# matrix.net
KiCad netlist of a schematic drawn in Altium Designer
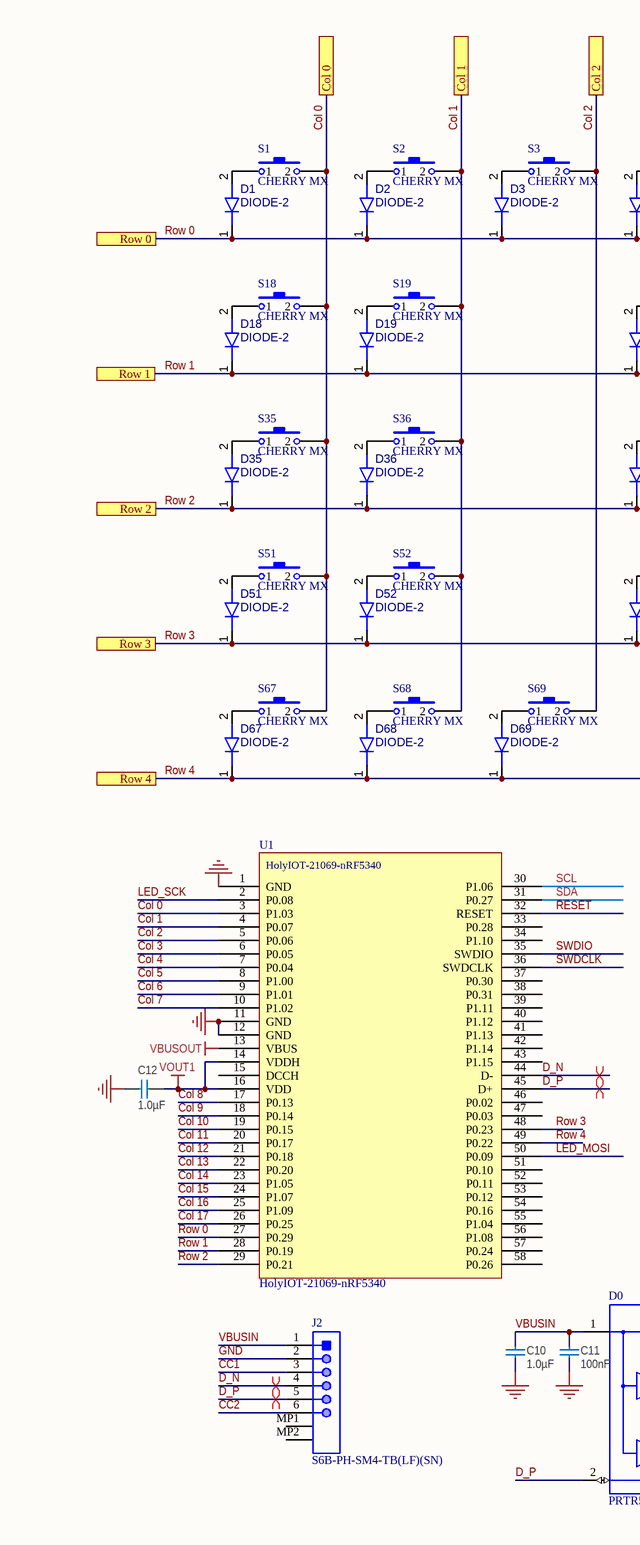
[diagram p0: matrix.SchDoc, left]
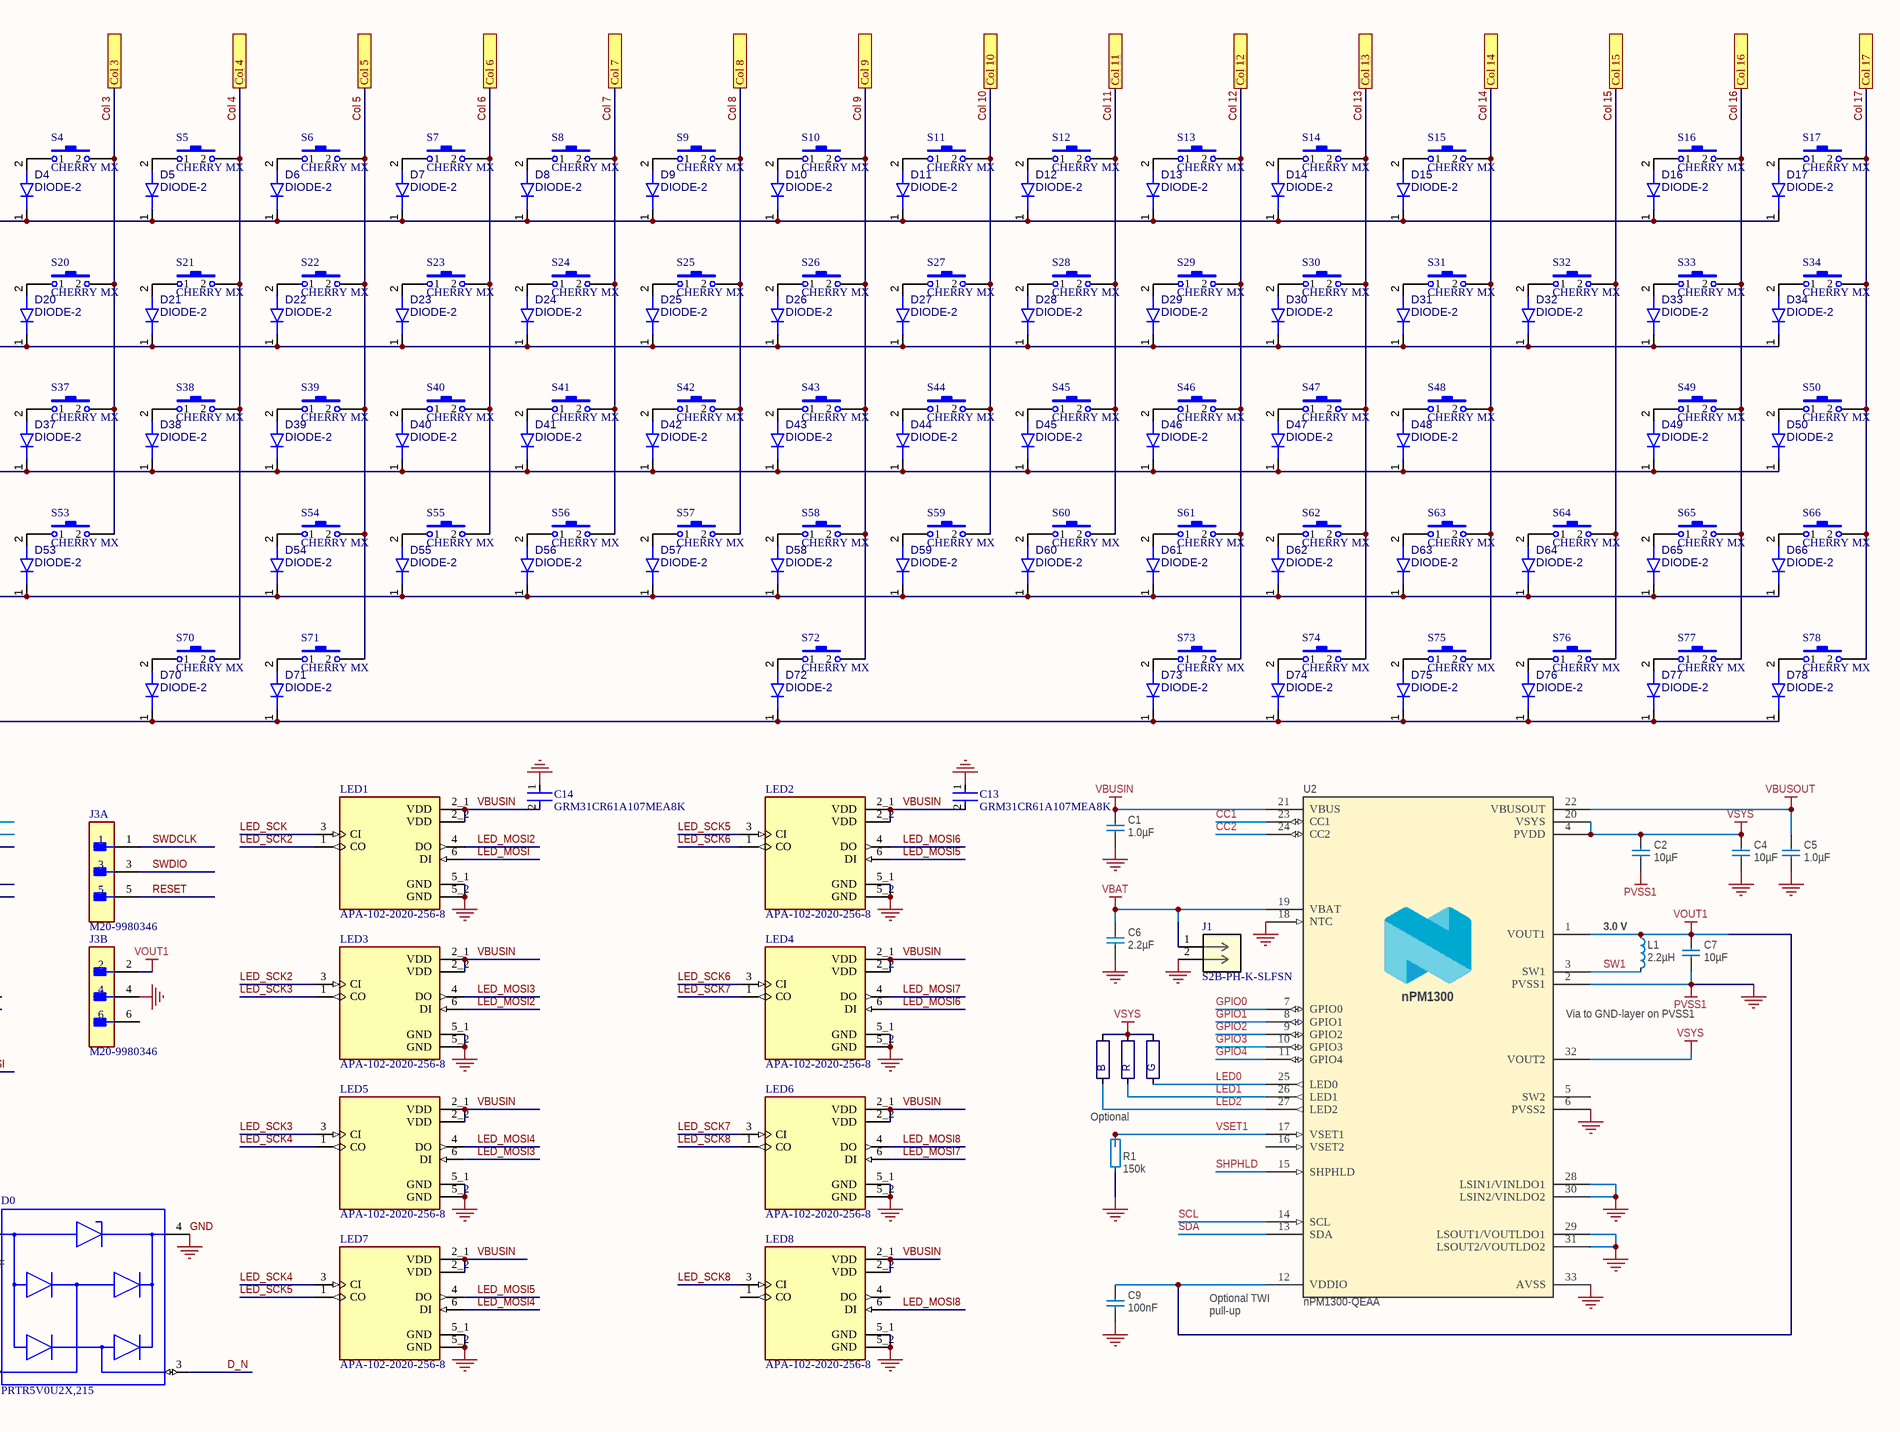
[diagram p1: matrix.SchDoc, right]

(export (version "E")
  (design (tool "Eeschema 10.0.6"))
  (components
    (comp (ref "B") (value "0603") (footprint "CAPC1608X06L") (libsource (lib "mitosis") (part "0603")))
    (comp (ref "C1")
      (value "1.0µF")
      (footprint "CAPC1608X06L")
      (description "Capacitor, Ceramic, 1.0µF 10V X5R 0603,±10%")
      (fields
        (field (name "PART NUMBER") "C0603-1µ0-10V-X5R")
        (field (name "MANUFACTURER") "N.A.")
        (field (name "AUTHOR") "getr")
      )
      (libsource (lib "npm1300_qeaa_config1") (part "C0603-1µ0-10V-X5R"))
    )
    (comp (ref "C2")
      (value "10µF")
      (footprint "CAPC1608X06L")
      (description "Capacitor, X5R, ±20%")
      (fields
        (field (name "PART NUMBER") "C0603-10µ")
        (field (name "MANUFACTURER") "N.A.")
        (field (name "AUTHOR") "rsk")
      )
      (libsource (lib "npm1300_qeaa_config1") (part "CAP"))
    )
    (comp (ref "C4")
      (value "10µF")
      (footprint "CAPC1608X06L")
      (description "Capacitor, X5R, ±20%")
      (fields
        (field (name "PART NUMBER") "C0603-10µ")
        (field (name "MANUFACTURER") "N.A.")
        (field (name "AUTHOR") "rsk")
      )
      (libsource (lib "npm1300_qeaa_config1") (part "CAP"))
    )
    (comp (ref "C5")
      (value "1.0µF")
      (footprint "CAPC1608X06L")
      (description "Capacitor, Ceramic, 1.0µF 10V X5R 0603,±10%")
      (fields
        (field (name "PART NUMBER") "C0603-1µ0-10V-X5R")
        (field (name "MANUFACTURER") "N.A.")
        (field (name "AUTHOR") "getr")
      )
      (libsource (lib "npm1300_qeaa_config1") (part "CAP"))
    )
    (comp (ref "C6")
      (value "2.2µF")
      (footprint "CAPC1608X06L")
      (description "Capacitor, Ceramic, X7R, ±10%, 16V")
      (fields
        (field (name "PART NUMBER") "C0603-2.2µ-16V-X7R")
        (field (name "MANUFACTURER") "Taiyo Yuden")
        (field (name "AUTHOR") "rsk")
      )
      (libsource (lib "npm1300_qeaa_config1") (part "CAP"))
    )
    (comp (ref "C7")
      (value "10µF")
      (footprint "CAPC1608X06L")
      (description "Capacitor, X5R, ±20%")
      (fields
        (field (name "PART NUMBER") "C0603-10µ")
        (field (name "MANUFACTURER") "N.A.")
        (field (name "AUTHOR") "rsk")
      )
      (libsource (lib "npm1300_qeaa_config1") (part "CAP"))
    )
    (comp (ref "C9")
      (value "100nF")
      (footprint "CAPC0603X03L_C")
      (description "Capacitor, X5R, ±10%")
      (fields
        (field (name "PART NUMBER") "C0201-100n")
        (field (name "MANUFACTURER") "N.A.")
        (field (name "AUTHOR") "rsk")
      )
      (libsource (lib "npm1300_qeaa_config1") (part "CAP"))
    )
    (comp (ref "C10")
      (value "1.0µF")
      (footprint "CAPC1608X06L")
      (description "Capacitor, Ceramic, 1.0µF 10V X5R 0603,±10%")
      (fields
        (field (name "PART NUMBER") "C0603-1µ0-10V-X5R")
        (field (name "MANUFACTURER") "N.A.")
        (field (name "AUTHOR") "getr")
      )
      (libsource (lib "npm1300_qeaa_config1") (part "C0603-1µ0-10V-X5R"))
    )
    (comp (ref "C11")
      (value "100nF")
      (footprint "CAPC0603X03L_C")
      (description "Capacitor, X5R, ±10%")
      (fields
        (field (name "PART NUMBER") "C0201-100n")
        (field (name "MANUFACTURER") "N.A.")
        (field (name "AUTHOR") "rsk")
      )
      (libsource (lib "npm1300_qeaa_config1") (part "C0201-100n"))
    )
    (comp (ref "C12")
      (value "1.0µF")
      (footprint "CAPC1608X06L")
      (description "Capacitor, Ceramic, 1.0µF 10V X5R 0603,±10%")
      (fields
        (field (name "PART NUMBER") "C0603-1µ0-10V-X5R")
        (field (name "MANUFACTURER") "N.A.")
        (field (name "AUTHOR") "getr")
      )
      (libsource (lib "npm1300_qeaa_config1") (part "C0603-1µ0-10V-X5R"))
    )
    (comp (ref "C13")
      (value "GRM31CR61A107MEA8K")
      (footprint "FP-GRM31C-0_3-e0_3_0_8-MFG")
      (description "Chip Multilayer Ceramic Capacitors for General Purpose, 1206, 100uF, X5R, 15%, 20%, 10V")
      (libsource (lib "Altium Content Vault") (part "f23184f103b6ebe33a8c269c53dcba6"))
    )
    (comp (ref "C14")
      (value "GRM31CR61A107MEA8K")
      (footprint "FP-GRM31C-0_3-e0_3_0_8-MFG")
      (description "Chip Multilayer Ceramic Capacitors for General Purpose, 1206, 100uF, X5R, 15%, 20%, 10V")
      (libsource (lib "Altium Content Vault") (part "f23184f103b6ebe33a8c269c53dcba6"))
    )
    (comp (ref "D0")
      (value "PRTR5V0U2X,215")
      (footprint "FP-SOT143B-MFG")
      (description "Trans Voltage Suppressor Diode, 5.5V V(RWM), Unidirectional, 1 Element, Silicon")
      (libsource (lib "NUSolar") (part "31e4fa1655694efd507c8a671e666ef"))
    )
    (comp (ref "D1")
      (value "DIODE-2")
      (footprint "1N4148")
      (description "Diode")
      (libsource (lib "mitosis") (part "1N4148"))
    )
    (comp (ref "D2")
      (value "DIODE-2")
      (footprint "1N4148")
      (description "Diode")
      (libsource (lib "mitosis") (part "1N4148"))
    )
    (comp (ref "D3")
      (value "DIODE-2")
      (footprint "1N4148")
      (description "Diode")
      (libsource (lib "mitosis") (part "1N4148"))
    )
    (comp (ref "D4")
      (value "DIODE-2")
      (footprint "1N4148")
      (description "Diode")
      (libsource (lib "mitosis") (part "1N4148"))
    )
    (comp (ref "D5")
      (value "DIODE-2")
      (footprint "1N4148")
      (description "Diode")
      (libsource (lib "mitosis") (part "1N4148"))
    )
    (comp (ref "D6")
      (value "DIODE-2")
      (footprint "1N4148")
      (description "Diode")
      (libsource (lib "mitosis") (part "1N4148"))
    )
    (comp (ref "D7")
      (value "DIODE-2")
      (footprint "1N4148")
      (description "Diode")
      (libsource (lib "mitosis") (part "1N4148"))
    )
    (comp (ref "D8")
      (value "DIODE-2")
      (footprint "1N4148")
      (description "Diode")
      (libsource (lib "mitosis") (part "1N4148"))
    )
    (comp (ref "D9")
      (value "DIODE-2")
      (footprint "1N4148")
      (description "Diode")
      (libsource (lib "mitosis") (part "1N4148"))
    )
    (comp (ref "D10")
      (value "DIODE-2")
      (footprint "1N4148")
      (description "Diode")
      (libsource (lib "mitosis") (part "1N4148"))
    )
    (comp (ref "D11")
      (value "DIODE-2")
      (footprint "1N4148")
      (description "Diode")
      (libsource (lib "mitosis") (part "1N4148"))
    )
    (comp (ref "D12")
      (value "DIODE-2")
      (footprint "1N4148")
      (description "Diode")
      (libsource (lib "mitosis") (part "1N4148"))
    )
    (comp (ref "D13")
      (value "DIODE-2")
      (footprint "1N4148")
      (description "Diode")
      (libsource (lib "mitosis") (part "1N4148"))
    )
    (comp (ref "D14")
      (value "DIODE-2")
      (footprint "1N4148")
      (description "Diode")
      (libsource (lib "mitosis") (part "1N4148"))
    )
    (comp (ref "D15")
      (value "DIODE-2")
      (footprint "1N4148")
      (description "Diode")
      (libsource (lib "mitosis") (part "1N4148"))
    )
    (comp (ref "D16")
      (value "DIODE-2")
      (footprint "1N4148")
      (description "Diode")
      (libsource (lib "mitosis") (part "1N4148"))
    )
    (comp (ref "D17")
      (value "DIODE-2")
      (footprint "1N4148")
      (description "Diode")
      (libsource (lib "mitosis") (part "1N4148"))
    )
    (comp (ref "D18")
      (value "DIODE-2")
      (footprint "1N4148")
      (description "Diode")
      (libsource (lib "mitosis") (part "1N4148"))
    )
    (comp (ref "D19")
      (value "DIODE-2")
      (footprint "1N4148")
      (description "Diode")
      (libsource (lib "mitosis") (part "1N4148"))
    )
    (comp (ref "D20")
      (value "DIODE-2")
      (footprint "1N4148")
      (description "Diode")
      (libsource (lib "mitosis") (part "1N4148"))
    )
    (comp (ref "D21")
      (value "DIODE-2")
      (footprint "1N4148")
      (description "Diode")
      (libsource (lib "mitosis") (part "1N4148"))
    )
    (comp (ref "D22")
      (value "DIODE-2")
      (footprint "1N4148")
      (description "Diode")
      (libsource (lib "mitosis") (part "1N4148"))
    )
    (comp (ref "D23")
      (value "DIODE-2")
      (footprint "1N4148")
      (description "Diode")
      (libsource (lib "mitosis") (part "1N4148"))
    )
    (comp (ref "D24")
      (value "DIODE-2")
      (footprint "1N4148")
      (description "Diode")
      (libsource (lib "mitosis") (part "1N4148"))
    )
    (comp (ref "D25")
      (value "DIODE-2")
      (footprint "1N4148")
      (description "Diode")
      (libsource (lib "mitosis") (part "1N4148"))
    )
    (comp (ref "D26")
      (value "DIODE-2")
      (footprint "1N4148")
      (description "Diode")
      (libsource (lib "mitosis") (part "1N4148"))
    )
    (comp (ref "D27")
      (value "DIODE-2")
      (footprint "1N4148")
      (description "Diode")
      (libsource (lib "mitosis") (part "1N4148"))
    )
    (comp (ref "D28")
      (value "DIODE-2")
      (footprint "1N4148")
      (description "Diode")
      (libsource (lib "mitosis") (part "1N4148"))
    )
    (comp (ref "D29")
      (value "DIODE-2")
      (footprint "1N4148")
      (description "Diode")
      (libsource (lib "mitosis") (part "1N4148"))
    )
    (comp (ref "D30")
      (value "DIODE-2")
      (footprint "1N4148")
      (description "Diode")
      (libsource (lib "mitosis") (part "1N4148"))
    )
    (comp (ref "D31")
      (value "DIODE-2")
      (footprint "1N4148")
      (description "Diode")
      (libsource (lib "mitosis") (part "1N4148"))
    )
    (comp (ref "D32")
      (value "DIODE-2")
      (footprint "1N4148")
      (description "Diode")
      (libsource (lib "mitosis") (part "1N4148"))
    )
    (comp (ref "D33")
      (value "DIODE-2")
      (footprint "1N4148")
      (description "Diode")
      (libsource (lib "mitosis") (part "1N4148"))
    )
    (comp (ref "D34")
      (value "DIODE-2")
      (footprint "1N4148")
      (description "Diode")
      (libsource (lib "mitosis") (part "1N4148"))
    )
    (comp (ref "D35")
      (value "DIODE-2")
      (footprint "1N4148")
      (description "Diode")
      (libsource (lib "mitosis") (part "1N4148"))
    )
    (comp (ref "D36")
      (value "DIODE-2")
      (footprint "1N4148")
      (description "Diode")
      (libsource (lib "mitosis") (part "1N4148"))
    )
    (comp (ref "D37")
      (value "DIODE-2")
      (footprint "1N4148")
      (description "Diode")
      (libsource (lib "mitosis") (part "1N4148"))
    )
    (comp (ref "D38")
      (value "DIODE-2")
      (footprint "1N4148")
      (description "Diode")
      (libsource (lib "mitosis") (part "1N4148"))
    )
    (comp (ref "D39")
      (value "DIODE-2")
      (footprint "1N4148")
      (description "Diode")
      (libsource (lib "mitosis") (part "1N4148"))
    )
    (comp (ref "D40")
      (value "DIODE-2")
      (footprint "1N4148")
      (description "Diode")
      (libsource (lib "mitosis") (part "1N4148"))
    )
    (comp (ref "D41")
      (value "DIODE-2")
      (footprint "1N4148")
      (description "Diode")
      (libsource (lib "mitosis") (part "1N4148"))
    )
    (comp (ref "D42")
      (value "DIODE-2")
      (footprint "1N4148")
      (description "Diode")
      (libsource (lib "mitosis") (part "1N4148"))
    )
    (comp (ref "D43")
      (value "DIODE-2")
      (footprint "1N4148")
      (description "Diode")
      (libsource (lib "mitosis") (part "1N4148"))
    )
    (comp (ref "D44")
      (value "DIODE-2")
      (footprint "1N4148")
      (description "Diode")
      (libsource (lib "mitosis") (part "1N4148"))
    )
    (comp (ref "D45")
      (value "DIODE-2")
      (footprint "1N4148")
      (description "Diode")
      (libsource (lib "mitosis") (part "1N4148"))
    )
    (comp (ref "D46")
      (value "DIODE-2")
      (footprint "1N4148")
      (description "Diode")
      (libsource (lib "mitosis") (part "1N4148"))
    )
    (comp (ref "D47")
      (value "DIODE-2")
      (footprint "1N4148")
      (description "Diode")
      (libsource (lib "mitosis") (part "1N4148"))
    )
    (comp (ref "D48")
      (value "DIODE-2")
      (footprint "1N4148")
      (description "Diode")
      (libsource (lib "mitosis") (part "1N4148"))
    )
    (comp (ref "D49")
      (value "DIODE-2")
      (footprint "1N4148")
      (description "Diode")
      (libsource (lib "mitosis") (part "1N4148"))
    )
    (comp (ref "D50")
      (value "DIODE-2")
      (footprint "1N4148")
      (description "Diode")
      (libsource (lib "mitosis") (part "1N4148"))
    )
    (comp (ref "D51")
      (value "DIODE-2")
      (footprint "1N4148")
      (description "Diode")
      (libsource (lib "mitosis") (part "1N4148"))
    )
    (comp (ref "D52")
      (value "DIODE-2")
      (footprint "1N4148")
      (description "Diode")
      (libsource (lib "mitosis") (part "1N4148"))
    )
    (comp (ref "D53")
      (value "DIODE-2")
      (footprint "1N4148")
      (description "Diode")
      (libsource (lib "mitosis") (part "1N4148"))
    )
    (comp (ref "D54")
      (value "DIODE-2")
      (footprint "1N4148")
      (description "Diode")
      (libsource (lib "mitosis") (part "1N4148"))
    )
    (comp (ref "D55")
      (value "DIODE-2")
      (footprint "1N4148")
      (description "Diode")
      (libsource (lib "mitosis") (part "1N4148"))
    )
    (comp (ref "D56")
      (value "DIODE-2")
      (footprint "1N4148")
      (description "Diode")
      (libsource (lib "mitosis") (part "1N4148"))
    )
    (comp (ref "D57")
      (value "DIODE-2")
      (footprint "1N4148")
      (description "Diode")
      (libsource (lib "mitosis") (part "1N4148"))
    )
    (comp (ref "D58")
      (value "DIODE-2")
      (footprint "1N4148")
      (description "Diode")
      (libsource (lib "mitosis") (part "1N4148"))
    )
    (comp (ref "D59")
      (value "DIODE-2")
      (footprint "1N4148")
      (description "Diode")
      (libsource (lib "mitosis") (part "1N4148"))
    )
    (comp (ref "D60")
      (value "DIODE-2")
      (footprint "1N4148")
      (description "Diode")
      (libsource (lib "mitosis") (part "1N4148"))
    )
    (comp (ref "D61")
      (value "DIODE-2")
      (footprint "1N4148")
      (description "Diode")
      (libsource (lib "mitosis") (part "1N4148"))
    )
    (comp (ref "D62")
      (value "DIODE-2")
      (footprint "1N4148")
      (description "Diode")
      (libsource (lib "mitosis") (part "1N4148"))
    )
    (comp (ref "D63")
      (value "DIODE-2")
      (footprint "1N4148")
      (description "Diode")
      (libsource (lib "mitosis") (part "1N4148"))
    )
    (comp (ref "D64")
      (value "DIODE-2")
      (footprint "1N4148")
      (description "Diode")
      (libsource (lib "mitosis") (part "1N4148"))
    )
    (comp (ref "D65")
      (value "DIODE-2")
      (footprint "1N4148")
      (description "Diode")
      (libsource (lib "mitosis") (part "1N4148"))
    )
    (comp (ref "D66")
      (value "DIODE-2")
      (footprint "1N4148")
      (description "Diode")
      (libsource (lib "mitosis") (part "1N4148"))
    )
    (comp (ref "D67")
      (value "DIODE-2")
      (footprint "1N4148")
      (description "Diode")
      (libsource (lib "mitosis") (part "1N4148"))
    )
    (comp (ref "D68")
      (value "DIODE-2")
      (footprint "1N4148")
      (description "Diode")
      (libsource (lib "mitosis") (part "1N4148"))
    )
    (comp (ref "D69")
      (value "DIODE-2")
      (footprint "1N4148")
      (description "Diode")
      (libsource (lib "mitosis") (part "1N4148"))
    )
    (comp (ref "D70")
      (value "DIODE-2")
      (footprint "1N4148")
      (description "Diode")
      (libsource (lib "mitosis") (part "1N4148"))
    )
    (comp (ref "D71")
      (value "DIODE-2")
      (footprint "1N4148")
      (description "Diode")
      (libsource (lib "mitosis") (part "1N4148"))
    )
    (comp (ref "D72")
      (value "DIODE-2")
      (footprint "1N4148")
      (description "Diode")
      (libsource (lib "mitosis") (part "1N4148"))
    )
    (comp (ref "D73")
      (value "DIODE-2")
      (footprint "1N4148")
      (description "Diode")
      (libsource (lib "mitosis") (part "1N4148"))
    )
    (comp (ref "D74")
      (value "DIODE-2")
      (footprint "1N4148")
      (description "Diode")
      (libsource (lib "mitosis") (part "1N4148"))
    )
    (comp (ref "D75")
      (value "DIODE-2")
      (footprint "1N4148")
      (description "Diode")
      (libsource (lib "mitosis") (part "1N4148"))
    )
    (comp (ref "D76")
      (value "DIODE-2")
      (footprint "1N4148")
      (description "Diode")
      (libsource (lib "mitosis") (part "1N4148"))
    )
    (comp (ref "D77")
      (value "DIODE-2")
      (footprint "1N4148")
      (description "Diode")
      (libsource (lib "mitosis") (part "1N4148"))
    )
    (comp (ref "D78")
      (value "DIODE-2")
      (footprint "1N4148")
      (description "Diode")
      (libsource (lib "mitosis") (part "1N4148"))
    )
    (comp (ref "G") (value "0603") (footprint "CAPC1608X06L") (libsource (lib "mitosis") (part "0603")))
    (comp (ref "J1")
      (value "S2B-PH-K-SLFSN")
      (footprint "CONN_S2B-PH-K-S_JST")
      (description "No Description Available")
      (libsource (lib "mitosis") (part "S2B-PH-K-SLFSN"))
    )
    (comp (ref "J2")
      (value "S6B-PH-SM4-TB(LF)(SN)")
      (footprint "JST-S6B-PH-SM4-TB(LF)(SN)_V")
      (description "Male Header, Pitch 2 mm, 1 x 6 Position, Height 5.5 mm, -25 to 85 degC")
      (fields (field (name "MANUFACTURER") "JST"))
      (libsource (lib "mitosis") (part "S6B-PH-SM4-TB"))
    )
    (comp (ref "J3")
      (value "M20-9980346")
      (footprint "FP-M20-9980346-MFG")
      (description "CONN HEADER VERT 6POS 2.54MM")
      (fields
        (field (name "MANUFACTURER") "Harwin")
        (field (name "OCTOPART") "https://octopart.com/m20-9980346-harwin-5436545")
      )
      (libsource (lib "mitosis") (part "CMP-2000-06636-2"))
    )
    (comp (ref "L1")
      (value "2.2µH")
      (footprint "INDC2016X10N")
      (description "Inductor, Irms=2.5A, Isat=2.9A, ±20%, DCR=73mΩ")
      (fields
        (field (name "PART NUMBER") "L0806-2µ2-2500mA-73mOhm-CIGT201610EH2R2MNE")
        (field (name "MANUFACTURER") "Samsung Electro-Mechanics")
        (field (name "AUTHOR") "rsk")
      )
      (libsource (lib "npm1300_qeaa_config1") (part "IND"))
    )
    (comp (ref "LED1")
      (value "APA-102-2020-256-8")
      (footprint "LED_APA-102-2020-256-8")
      (description "8-pin type LED three-color RGB Dimming control")
      (fields (field (name "MF") "iPixel LED Light Co."))
      (libsource (lib "mitosis") (part "APA-102-2020-256-8"))
    )
    (comp (ref "LED2")
      (value "APA-102-2020-256-8")
      (footprint "LED_APA-102-2020-256-8")
      (description "8-pin type LED three-color RGB Dimming control")
      (fields (field (name "MF") "iPixel LED Light Co."))
      (libsource (lib "mitosis") (part "APA-102-2020-256-8"))
    )
    (comp (ref "LED3")
      (value "APA-102-2020-256-8")
      (footprint "LED_APA-102-2020-256-8")
      (description "8-pin type LED three-color RGB Dimming control")
      (fields (field (name "MF") "iPixel LED Light Co."))
      (libsource (lib "mitosis") (part "APA-102-2020-256-8"))
    )
    (comp (ref "LED4")
      (value "APA-102-2020-256-8")
      (footprint "LED_APA-102-2020-256-8")
      (description "8-pin type LED three-color RGB Dimming control")
      (fields (field (name "MF") "iPixel LED Light Co."))
      (libsource (lib "mitosis") (part "APA-102-2020-256-8"))
    )
    (comp (ref "LED5")
      (value "APA-102-2020-256-8")
      (footprint "LED_APA-102-2020-256-8")
      (description "8-pin type LED three-color RGB Dimming control")
      (fields (field (name "MF") "iPixel LED Light Co."))
      (libsource (lib "mitosis") (part "APA-102-2020-256-8"))
    )
    (comp (ref "LED6")
      (value "APA-102-2020-256-8")
      (footprint "LED_APA-102-2020-256-8")
      (description "8-pin type LED three-color RGB Dimming control")
      (fields (field (name "MF") "iPixel LED Light Co."))
      (libsource (lib "mitosis") (part "APA-102-2020-256-8"))
    )
    (comp (ref "LED7")
      (value "APA-102-2020-256-8")
      (footprint "LED_APA-102-2020-256-8")
      (description "8-pin type LED three-color RGB Dimming control")
      (fields (field (name "MF") "iPixel LED Light Co."))
      (libsource (lib "mitosis") (part "APA-102-2020-256-8"))
    )
    (comp (ref "LED8")
      (value "APA-102-2020-256-8")
      (footprint "LED_APA-102-2020-256-8")
      (description "8-pin type LED three-color RGB Dimming control")
      (fields (field (name "MF") "iPixel LED Light Co."))
      (libsource (lib "mitosis") (part "APA-102-2020-256-8"))
    )
    (comp (ref "R") (value "0603") (footprint "CAPC1608X06L") (libsource (lib "mitosis") (part "0603")))
    (comp (ref "R1")
      (value "150k")
      (footprint "RESC0603X03L_C")
      (description "Resistor, ±1%, 0.05W")
      (fields
        (field (name "PART NUMBER") "R0201-150k")
        (field (name "MANUFACTURER") "N.A.")
        (field (name "AUTHOR") "rsk")
      )
      (libsource (lib "npm1300_qeaa_config1") (part "R0201-150k"))
    )
    (comp (ref "S1")
      (value "CHERRY MX")
      (footprint "1u-CHERRY-SMK-CUTOUT")
      (description "Switch")
      (fields (field (name "PUBLISHER") "Altium Limited"))
      (libsource (lib "mitosis") (part "CHERRY MX"))
    )
    (comp (ref "S2")
      (value "CHERRY MX")
      (footprint "1u-CHERRY-SMK-CUTOUT")
      (description "Switch")
      (fields (field (name "PUBLISHER") "Altium Limited"))
      (libsource (lib "mitosis") (part "CHERRY MX"))
    )
    (comp (ref "S3")
      (value "CHERRY MX")
      (footprint "1u-CHERRY-SMK-CUTOUT")
      (description "Switch")
      (fields (field (name "PUBLISHER") "Altium Limited"))
      (libsource (lib "mitosis") (part "CHERRY MX"))
    )
    (comp (ref "S4")
      (value "CHERRY MX")
      (footprint "1u-CHERRY-SMK-CUTOUT")
      (description "Switch")
      (fields (field (name "PUBLISHER") "Altium Limited"))
      (libsource (lib "mitosis") (part "CHERRY MX"))
    )
    (comp (ref "S5")
      (value "CHERRY MX")
      (footprint "1u-CHERRY-SMK-CUTOUT")
      (description "Switch")
      (fields (field (name "PUBLISHER") "Altium Limited"))
      (libsource (lib "mitosis") (part "CHERRY MX"))
    )
    (comp (ref "S6")
      (value "CHERRY MX")
      (footprint "1u-CHERRY-SMK-CUTOUT")
      (description "Switch")
      (fields (field (name "PUBLISHER") "Altium Limited"))
      (libsource (lib "mitosis") (part "CHERRY MX"))
    )
    (comp (ref "S7")
      (value "CHERRY MX")
      (footprint "1u-CHERRY-SMK-CUTOUT")
      (description "Switch")
      (fields (field (name "PUBLISHER") "Altium Limited"))
      (libsource (lib "mitosis") (part "CHERRY MX"))
    )
    (comp (ref "S8")
      (value "CHERRY MX")
      (footprint "1u-CHERRY-SMK-CUTOUT")
      (description "Switch")
      (fields (field (name "PUBLISHER") "Altium Limited"))
      (libsource (lib "mitosis") (part "CHERRY MX"))
    )
    (comp (ref "S9")
      (value "CHERRY MX")
      (footprint "1u-CHERRY-SMK-CUTOUT")
      (description "Switch")
      (fields (field (name "PUBLISHER") "Altium Limited"))
      (libsource (lib "mitosis") (part "CHERRY MX"))
    )
    (comp (ref "S10")
      (value "CHERRY MX")
      (footprint "1u-CHERRY-SMK-CUTOUT")
      (description "Switch")
      (fields (field (name "PUBLISHER") "Altium Limited"))
      (libsource (lib "mitosis") (part "CHERRY MX"))
    )
    (comp (ref "S11")
      (value "CHERRY MX")
      (footprint "1u-CHERRY-SMK-CUTOUT")
      (description "Switch")
      (fields (field (name "PUBLISHER") "Altium Limited"))
      (libsource (lib "mitosis") (part "CHERRY MX"))
    )
    (comp (ref "S12")
      (value "CHERRY MX")
      (footprint "1u-CHERRY-SMK-CUTOUT")
      (description "Switch")
      (fields (field (name "PUBLISHER") "Altium Limited"))
      (libsource (lib "mitosis") (part "CHERRY MX"))
    )
    (comp (ref "S13")
      (value "CHERRY MX")
      (footprint "1u-CHERRY-SMK-CUTOUT")
      (description "Switch")
      (fields (field (name "PUBLISHER") "Altium Limited"))
      (libsource (lib "mitosis") (part "CHERRY MX"))
    )
    (comp (ref "S14")
      (value "CHERRY MX")
      (footprint "1u-CHERRY-SMK-CUTOUT")
      (description "Switch")
      (fields (field (name "PUBLISHER") "Altium Limited"))
      (libsource (lib "mitosis") (part "CHERRY MX"))
    )
    (comp (ref "S15")
      (value "CHERRY MX")
      (footprint "1u-CHERRY-SMK-CUTOUT")
      (description "Switch")
      (fields (field (name "PUBLISHER") "Altium Limited"))
      (libsource (lib "mitosis") (part "CHERRY MX"))
    )
    (comp (ref "S16")
      (value "CHERRY MX")
      (footprint "2u-STAB-CHERRY-SMK-CUTOUT")
      (description "Switch")
      (fields (field (name "PUBLISHER") "Altium Limited"))
      (libsource (lib "mitosis") (part "CHERRY MX"))
    )
    (comp (ref "S17")
      (value "CHERRY MX")
      (footprint "1u-CHERRY-SMK-CUTOUT")
      (description "Switch")
      (fields (field (name "PUBLISHER") "Altium Limited"))
      (libsource (lib "mitosis") (part "CHERRY MX"))
    )
    (comp (ref "S18")
      (value "CHERRY MX")
      (footprint "1u-CHERRY-SMK-CUTOUT")
      (description "Switch")
      (fields (field (name "PUBLISHER") "Altium Limited"))
      (libsource (lib "mitosis") (part "CHERRY MX"))
    )
    (comp (ref "S19")
      (value "CHERRY MX")
      (footprint "1u-CHERRY-SMK-CUTOUT")
      (description "Switch")
      (fields (field (name "PUBLISHER") "Altium Limited"))
      (libsource (lib "mitosis") (part "CHERRY MX"))
    )
    (comp (ref "S20")
      (value "CHERRY MX")
      (footprint "1.5u-CHERRY-SMK-CUTOUT")
      (description "Switch")
      (fields (field (name "PUBLISHER") "Altium Limited"))
      (libsource (lib "mitosis") (part "CHERRY MX"))
    )
    (comp (ref "S21")
      (value "CHERRY MX")
      (footprint "1u-CHERRY-SMK-CUTOUT")
      (description "Switch")
      (fields (field (name "PUBLISHER") "Altium Limited"))
      (libsource (lib "mitosis") (part "CHERRY MX"))
    )
    (comp (ref "S22")
      (value "CHERRY MX")
      (footprint "1u-CHERRY-SMK-CUTOUT")
      (description "Switch")
      (fields (field (name "PUBLISHER") "Altium Limited"))
      (libsource (lib "mitosis") (part "CHERRY MX"))
    )
    (comp (ref "S23")
      (value "CHERRY MX")
      (footprint "1u-CHERRY-SMK-CUTOUT")
      (description "Switch")
      (fields (field (name "PUBLISHER") "Altium Limited"))
      (libsource (lib "mitosis") (part "CHERRY MX"))
    )
    (comp (ref "S24")
      (value "CHERRY MX")
      (footprint "1u-CHERRY-SMK-CUTOUT")
      (description "Switch")
      (fields (field (name "PUBLISHER") "Altium Limited"))
      (libsource (lib "mitosis") (part "CHERRY MX"))
    )
    (comp (ref "S25")
      (value "CHERRY MX")
      (footprint "1u-CHERRY-SMK-CUTOUT")
      (description "Switch")
      (fields (field (name "PUBLISHER") "Altium Limited"))
      (libsource (lib "mitosis") (part "CHERRY MX"))
    )
    (comp (ref "S26")
      (value "CHERRY MX")
      (footprint "1u-CHERRY-SMK-CUTOUT")
      (description "Switch")
      (fields (field (name "PUBLISHER") "Altium Limited"))
      (libsource (lib "mitosis") (part "CHERRY MX"))
    )
    (comp (ref "S27")
      (value "CHERRY MX")
      (footprint "1u-CHERRY-SMK-CUTOUT")
      (description "Switch")
      (fields (field (name "PUBLISHER") "Altium Limited"))
      (libsource (lib "mitosis") (part "CHERRY MX"))
    )
    (comp (ref "S28")
      (value "CHERRY MX")
      (footprint "1u-CHERRY-SMK-CUTOUT")
      (description "Switch")
      (fields (field (name "PUBLISHER") "Altium Limited"))
      (libsource (lib "mitosis") (part "CHERRY MX"))
    )
    (comp (ref "S29")
      (value "CHERRY MX")
      (footprint "1u-CHERRY-SMK-CUTOUT")
      (description "Switch")
      (fields (field (name "PUBLISHER") "Altium Limited"))
      (libsource (lib "mitosis") (part "CHERRY MX"))
    )
    (comp (ref "S30")
      (value "CHERRY MX")
      (footprint "1u-CHERRY-SMK-CUTOUT")
      (description "Switch")
      (fields (field (name "PUBLISHER") "Altium Limited"))
      (libsource (lib "mitosis") (part "CHERRY MX"))
    )
    (comp (ref "S31")
      (value "CHERRY MX")
      (footprint "1u-CHERRY-SMK-CUTOUT")
      (description "Switch")
      (fields (field (name "PUBLISHER") "Altium Limited"))
      (libsource (lib "mitosis") (part "CHERRY MX"))
    )
    (comp (ref "S32")
      (value "CHERRY MX")
      (footprint "1u-CHERRY-SMK-CUTOUT")
      (description "Switch")
      (fields (field (name "PUBLISHER") "Altium Limited"))
      (libsource (lib "mitosis") (part "CHERRY MX"))
    )
    (comp (ref "S33")
      (value "CHERRY MX")
      (footprint "1.5u-CHERRY-SMK-CUTOUT")
      (description "Switch")
      (fields (field (name "PUBLISHER") "Altium Limited"))
      (libsource (lib "mitosis") (part "CHERRY MX"))
    )
    (comp (ref "S34")
      (value "CHERRY MX")
      (footprint "1u-CHERRY-SMK-CUTOUT")
      (description "Switch")
      (fields (field (name "PUBLISHER") "Altium Limited"))
      (libsource (lib "mitosis") (part "CHERRY MX"))
    )
    (comp (ref "S35")
      (value "CHERRY MX")
      (footprint "1u-CHERRY-SMK-CUTOUT")
      (description "Switch")
      (fields (field (name "PUBLISHER") "Altium Limited"))
      (libsource (lib "mitosis") (part "CHERRY MX"))
    )
    (comp (ref "S36")
      (value "CHERRY MX")
      (footprint "1u-CHERRY-SMK-CUTOUT")
      (description "Switch")
      (fields (field (name "PUBLISHER") "Altium Limited"))
      (libsource (lib "mitosis") (part "CHERRY MX"))
    )
    (comp (ref "S37")
      (value "CHERRY MX")
      (footprint "1.75u-CHERRY-SMK-CUTOUT")
      (description "Switch")
      (fields (field (name "PUBLISHER") "Altium Limited"))
      (libsource (lib "mitosis") (part "CHERRY MX"))
    )
    (comp (ref "S38")
      (value "CHERRY MX")
      (footprint "1u-CHERRY-SMK-CUTOUT")
      (description "Switch")
      (fields (field (name "PUBLISHER") "Altium Limited"))
      (libsource (lib "mitosis") (part "CHERRY MX"))
    )
    (comp (ref "S39")
      (value "CHERRY MX")
      (footprint "1u-CHERRY-SMK-CUTOUT")
      (description "Switch")
      (fields (field (name "PUBLISHER") "Altium Limited"))
      (libsource (lib "mitosis") (part "CHERRY MX"))
    )
    (comp (ref "S40")
      (value "CHERRY MX")
      (footprint "1u-CHERRY-SMK-CUTOUT")
      (description "Switch")
      (fields (field (name "PUBLISHER") "Altium Limited"))
      (libsource (lib "mitosis") (part "CHERRY MX"))
    )
    (comp (ref "S41")
      (value "CHERRY MX")
      (footprint "1u-CHERRY-SMK-CUTOUT")
      (description "Switch")
      (fields (field (name "PUBLISHER") "Altium Limited"))
      (libsource (lib "mitosis") (part "CHERRY MX"))
    )
    (comp (ref "S42")
      (value "CHERRY MX")
      (footprint "1u-CHERRY-SMK-CUTOUT")
      (description "Switch")
      (fields (field (name "PUBLISHER") "Altium Limited"))
      (libsource (lib "mitosis") (part "CHERRY MX"))
    )
    (comp (ref "S43")
      (value "CHERRY MX")
      (footprint "1u-CHERRY-SMK-CUTOUT")
      (description "Switch")
      (fields (field (name "PUBLISHER") "Altium Limited"))
      (libsource (lib "mitosis") (part "CHERRY MX"))
    )
    (comp (ref "S44")
      (value "CHERRY MX")
      (footprint "1u-CHERRY-SMK-CUTOUT")
      (description "Switch")
      (fields (field (name "PUBLISHER") "Altium Limited"))
      (libsource (lib "mitosis") (part "CHERRY MX"))
    )
    (comp (ref "S45")
      (value "CHERRY MX")
      (footprint "1u-CHERRY-SMK-CUTOUT")
      (description "Switch")
      (fields (field (name "PUBLISHER") "Altium Limited"))
      (libsource (lib "mitosis") (part "CHERRY MX"))
    )
    (comp (ref "S46")
      (value "CHERRY MX")
      (footprint "1u-CHERRY-SMK-CUTOUT")
      (description "Switch")
      (fields (field (name "PUBLISHER") "Altium Limited"))
      (libsource (lib "mitosis") (part "CHERRY MX"))
    )
    (comp (ref "S47")
      (value "CHERRY MX")
      (footprint "1u-CHERRY-SMK-CUTOUT")
      (description "Switch")
      (fields (field (name "PUBLISHER") "Altium Limited"))
      (libsource (lib "mitosis") (part "CHERRY MX"))
    )
    (comp (ref "S48")
      (value "CHERRY MX")
      (footprint "1u-CHERRY-SMK-CUTOUT")
      (description "Switch")
      (fields (field (name "PUBLISHER") "Altium Limited"))
      (libsource (lib "mitosis") (part "CHERRY MX"))
    )
    (comp (ref "S49")
      (value "CHERRY MX")
      (footprint "2.25u-STAB-CHERRY-SMK-CUTOUT")
      (description "Switch")
      (fields (field (name "PUBLISHER") "Altium Limited"))
      (libsource (lib "mitosis") (part "CHERRY MX"))
    )
    (comp (ref "S50")
      (value "CHERRY MX")
      (footprint "1u-CHERRY-SMK-CUTOUT")
      (description "Switch")
      (fields (field (name "PUBLISHER") "Altium Limited"))
      (libsource (lib "mitosis") (part "CHERRY MX"))
    )
    (comp (ref "S51")
      (value "CHERRY MX")
      (footprint "1u-CHERRY-SMK-CUTOUT")
      (description "Switch")
      (fields (field (name "PUBLISHER") "Altium Limited"))
      (libsource (lib "mitosis") (part "CHERRY MX"))
    )
    (comp (ref "S52")
      (value "CHERRY MX")
      (footprint "1u-CHERRY-SMK-CUTOUT")
      (description "Switch")
      (fields (field (name "PUBLISHER") "Altium Limited"))
      (libsource (lib "mitosis") (part "CHERRY MX"))
    )
    (comp (ref "S53")
      (value "CHERRY MX")
      (footprint "2.25u-STAB-CHERRY-SMK-CUTOUT")
      (description "Switch")
      (fields (field (name "PUBLISHER") "Altium Limited"))
      (libsource (lib "mitosis") (part "CHERRY MX"))
    )
    (comp (ref "S54")
      (value "CHERRY MX")
      (footprint "1u-CHERRY-SMK-CUTOUT")
      (description "Switch")
      (fields (field (name "PUBLISHER") "Altium Limited"))
      (libsource (lib "mitosis") (part "CHERRY MX"))
    )
    (comp (ref "S55")
      (value "CHERRY MX")
      (footprint "1u-CHERRY-SMK-CUTOUT")
      (description "Switch")
      (fields (field (name "PUBLISHER") "Altium Limited"))
      (libsource (lib "mitosis") (part "CHERRY MX"))
    )
    (comp (ref "S56")
      (value "CHERRY MX")
      (footprint "1u-CHERRY-SMK-CUTOUT")
      (description "Switch")
      (fields (field (name "PUBLISHER") "Altium Limited"))
      (libsource (lib "mitosis") (part "CHERRY MX"))
    )
    (comp (ref "S57")
      (value "CHERRY MX")
      (footprint "1u-CHERRY-SMK-CUTOUT")
      (description "Switch")
      (fields (field (name "PUBLISHER") "Altium Limited"))
      (libsource (lib "mitosis") (part "CHERRY MX"))
    )
    (comp (ref "S58")
      (value "CHERRY MX")
      (footprint "1u-CHERRY-SMK-CUTOUT")
      (description "Switch")
      (fields (field (name "PUBLISHER") "Altium Limited"))
      (libsource (lib "mitosis") (part "CHERRY MX"))
    )
    (comp (ref "S59")
      (value "CHERRY MX")
      (footprint "1u-CHERRY-SMK-CUTOUT")
      (description "Switch")
      (fields (field (name "PUBLISHER") "Altium Limited"))
      (libsource (lib "mitosis") (part "CHERRY MX"))
    )
    (comp (ref "S60")
      (value "CHERRY MX")
      (footprint "1u-CHERRY-SMK-CUTOUT")
      (description "Switch")
      (fields (field (name "PUBLISHER") "Altium Limited"))
      (libsource (lib "mitosis") (part "CHERRY MX"))
    )
    (comp (ref "S61")
      (value "CHERRY MX")
      (footprint "1u-CHERRY-SMK-CUTOUT")
      (description "Switch")
      (fields (field (name "PUBLISHER") "Altium Limited"))
      (libsource (lib "mitosis") (part "CHERRY MX"))
    )
    (comp (ref "S62")
      (value "CHERRY MX")
      (footprint "1u-CHERRY-SMK-CUTOUT")
      (description "Switch")
      (fields (field (name "PUBLISHER") "Altium Limited"))
      (libsource (lib "mitosis") (part "CHERRY MX"))
    )
    (comp (ref "S63")
      (value "CHERRY MX")
      (footprint "1u-CHERRY-SMK-CUTOUT")
      (description "Switch")
      (fields (field (name "PUBLISHER") "Altium Limited"))
      (libsource (lib "mitosis") (part "CHERRY MX"))
    )
    (comp (ref "S64")
      (value "CHERRY MX")
      (footprint "1.75u-CHERRY-SMK-CUTOUT")
      (description "Switch")
      (fields (field (name "PUBLISHER") "Altium Limited"))
      (libsource (lib "mitosis") (part "CHERRY MX"))
    )
    (comp (ref "S65")
      (value "CHERRY MX")
      (footprint "1u-CHERRY-SMK-CUTOUT")
      (description "Switch")
      (fields (field (name "PUBLISHER") "Altium Limited"))
      (libsource (lib "mitosis") (part "CHERRY MX"))
    )
    (comp (ref "S66")
      (value "CHERRY MX")
      (footprint "1u-CHERRY-SMK-CUTOUT")
      (description "Switch")
      (fields (field (name "PUBLISHER") "Altium Limited"))
      (libsource (lib "mitosis") (part "CHERRY MX"))
    )
    (comp (ref "S67")
      (value "CHERRY MX")
      (footprint "1u-CHERRY-SMK-CUTOUT")
      (description "Switch")
      (fields (field (name "PUBLISHER") "Altium Limited"))
      (libsource (lib "mitosis") (part "CHERRY MX"))
    )
    (comp (ref "S68")
      (value "CHERRY MX")
      (footprint "1u-CHERRY-SMK-CUTOUT")
      (description "Switch")
      (fields (field (name "PUBLISHER") "Altium Limited"))
      (libsource (lib "mitosis") (part "CHERRY MX"))
    )
    (comp (ref "S69")
      (value "CHERRY MX")
      (footprint "1.25u-CHERRY-SMK-CUTOUT")
      (description "Switch")
      (fields (field (name "PUBLISHER") "Altium Limited"))
      (libsource (lib "mitosis") (part "CHERRY MX"))
    )
    (comp (ref "S70")
      (value "CHERRY MX")
      (footprint "1.25u-CHERRY-SMK-CUTOUT")
      (description "Switch")
      (fields (field (name "PUBLISHER") "Altium Limited"))
      (libsource (lib "mitosis") (part "CHERRY MX"))
    )
    (comp (ref "S71")
      (value "CHERRY MX")
      (footprint "1.25u-CHERRY-SMK-CUTOUT")
      (description "Switch")
      (fields (field (name "PUBLISHER") "Altium Limited"))
      (libsource (lib "mitosis") (part "CHERRY MX"))
    )
    (comp (ref "S72")
      (value "CHERRY MX")
      (footprint "6.25u-STAB-CHERRY-SMK-CUTOUT")
      (description "Switch")
      (fields (field (name "PUBLISHER") "Altium Limited"))
      (libsource (lib "mitosis") (part "CHERRY MX"))
    )
    (comp (ref "S73")
      (value "CHERRY MX")
      (footprint "1u-CHERRY-SMK-CUTOUT")
      (description "Switch")
      (fields (field (name "PUBLISHER") "Altium Limited"))
      (libsource (lib "mitosis") (part "CHERRY MX"))
    )
    (comp (ref "S74")
      (value "CHERRY MX")
      (footprint "1u-CHERRY-SMK-CUTOUT")
      (description "Switch")
      (fields (field (name "PUBLISHER") "Altium Limited"))
      (libsource (lib "mitosis") (part "CHERRY MX"))
    )
    (comp (ref "S75")
      (value "CHERRY MX")
      (footprint "1u-CHERRY-SMK-CUTOUT")
      (description "Switch")
      (fields (field (name "PUBLISHER") "Altium Limited"))
      (libsource (lib "mitosis") (part "CHERRY MX"))
    )
    (comp (ref "S76")
      (value "CHERRY MX")
      (footprint "1u-CHERRY-SMK-CUTOUT")
      (description "Switch")
      (fields (field (name "PUBLISHER") "Altium Limited"))
      (libsource (lib "mitosis") (part "CHERRY MX"))
    )
    (comp (ref "S77")
      (value "CHERRY MX")
      (footprint "1u-CHERRY-SMK-CUTOUT")
      (description "Switch")
      (fields (field (name "PUBLISHER") "Altium Limited"))
      (libsource (lib "mitosis") (part "CHERRY MX"))
    )
    (comp (ref "S78")
      (value "CHERRY MX")
      (footprint "1u-CHERRY-SMK-CUTOUT")
      (description "Switch")
      (fields (field (name "PUBLISHER") "Altium Limited"))
      (libsource (lib "mitosis") (part "CHERRY MX"))
    )
    (comp (ref "U1")
      (value "HolyIOT-21069-nRF5340")
      (footprint "HolyIOT-21069-nRF5340")
      (libsource (lib "mitosis") (part "HolyIOT-21069-nRF5340"))
    )
    (comp (ref "U2")
      (value "nPM1300-QEAA")
      (footprint "Nordic_QFN50P500X500X90-33N")
      (fields (field (name "MANUFACTURER") "Nordic Semiconductor") (field (name "AUTHOR") "eisk"))
      (libsource (lib "npm1300_qeaa_config1") (part "nPM1300_QEAA"))
    )
  )
  (nets
    (net (code "1") (name "/CC1") (class "Default")
      (node (ref "J2") (pin "3") (pinfunction "3_3") (pintype "passive"))
      (node (ref "U2") (pin "23") (pinfunction "CC1_23") (pintype "bidirectional"))
    )
    (net (code "2") (name "/CC2") (class "Default")
      (node (ref "J2") (pin "6") (pinfunction "6_6") (pintype "passive"))
      (node (ref "U2") (pin "24") (pinfunction "CC2_24") (pintype "bidirectional"))
    )
    (net (code "3") (name "/Col 0") (class "Default")
      (node (ref "S1") (pin "2") (pinfunction "2_2") (pintype "passive"))
      (node (ref "S18") (pin "2") (pinfunction "2_2") (pintype "passive"))
      (node (ref "S35") (pin "2") (pinfunction "2_2") (pintype "passive"))
      (node (ref "S51") (pin "2") (pinfunction "2_2") (pintype "passive"))
      (node (ref "S67") (pin "2") (pinfunction "2_2") (pintype "passive"))
      (node (ref "U1") (pin "3") (pinfunction "P1.03_3") (pintype "passive"))
    )
    (net (code "4") (name "/Col 1") (class "Default")
      (node (ref "S19") (pin "2") (pinfunction "2_2") (pintype "passive"))
      (node (ref "S2") (pin "2") (pinfunction "2_2") (pintype "passive"))
      (node (ref "S36") (pin "2") (pinfunction "2_2") (pintype "passive"))
      (node (ref "S52") (pin "2") (pinfunction "2_2") (pintype "passive"))
      (node (ref "S68") (pin "2") (pinfunction "2_2") (pintype "passive"))
      (node (ref "U1") (pin "4") (pinfunction "P0.07_4") (pintype "passive"))
    )
    (net (code "5") (name "/Col 2") (class "Default")
      (node (ref "S3") (pin "2") (pinfunction "2_2") (pintype "passive"))
      (node (ref "S69") (pin "2") (pinfunction "2_2") (pintype "passive"))
      (node (ref "U1") (pin "5") (pinfunction "P0.06_5") (pintype "passive"))
    )
    (net (code "6") (name "/Col 3") (class "Default")
      (node (ref "S20") (pin "2") (pinfunction "2_2") (pintype "passive"))
      (node (ref "S37") (pin "2") (pinfunction "2_2") (pintype "passive"))
      (node (ref "S4") (pin "2") (pinfunction "2_2") (pintype "passive"))
      (node (ref "S53") (pin "2") (pinfunction "2_2") (pintype "passive"))
      (node (ref "U1") (pin "6") (pinfunction "P0.05_6") (pintype "passive"))
    )
    (net (code "7") (name "/Col 4") (class "Default")
      (node (ref "S21") (pin "2") (pinfunction "2_2") (pintype "passive"))
      (node (ref "S38") (pin "2") (pinfunction "2_2") (pintype "passive"))
      (node (ref "S5") (pin "2") (pinfunction "2_2") (pintype "passive"))
      (node (ref "S70") (pin "2") (pinfunction "2_2") (pintype "passive"))
      (node (ref "U1") (pin "7") (pinfunction "P0.04_7") (pintype "passive"))
    )
    (net (code "8") (name "/Col 5") (class "Default")
      (node (ref "S22") (pin "2") (pinfunction "2_2") (pintype "passive"))
      (node (ref "S39") (pin "2") (pinfunction "2_2") (pintype "passive"))
      (node (ref "S54") (pin "2") (pinfunction "2_2") (pintype "passive"))
      (node (ref "S6") (pin "2") (pinfunction "2_2") (pintype "passive"))
      (node (ref "S71") (pin "2") (pinfunction "2_2") (pintype "passive"))
      (node (ref "U1") (pin "8") (pinfunction "P1.00_8") (pintype "passive"))
    )
    (net (code "9") (name "/Col 6") (class "Default")
      (node (ref "S23") (pin "2") (pinfunction "2_2") (pintype "passive"))
      (node (ref "S40") (pin "2") (pinfunction "2_2") (pintype "passive"))
      (node (ref "S55") (pin "2") (pinfunction "2_2") (pintype "passive"))
      (node (ref "S7") (pin "2") (pinfunction "2_2") (pintype "passive"))
      (node (ref "U1") (pin "9") (pinfunction "P1.01_9") (pintype "passive"))
    )
    (net (code "10") (name "/Col 7") (class "Default")
      (node (ref "S24") (pin "2") (pinfunction "2_2") (pintype "passive"))
      (node (ref "S41") (pin "2") (pinfunction "2_2") (pintype "passive"))
      (node (ref "S56") (pin "2") (pinfunction "2_2") (pintype "passive"))
      (node (ref "S8") (pin "2") (pinfunction "2_2") (pintype "passive"))
      (node (ref "U1") (pin "10") (pinfunction "P1.02_10") (pintype "passive"))
    )
    (net (code "11") (name "/Col 8") (class "Default")
      (node (ref "S25") (pin "2") (pinfunction "2_2") (pintype "passive"))
      (node (ref "S42") (pin "2") (pinfunction "2_2") (pintype "passive"))
      (node (ref "S57") (pin "2") (pinfunction "2_2") (pintype "passive"))
      (node (ref "S9") (pin "2") (pinfunction "2_2") (pintype "passive"))
      (node (ref "U1") (pin "17") (pinfunction "P0.13_17") (pintype "passive"))
    )
    (net (code "12") (name "/Col 9") (class "Default")
      (node (ref "S10") (pin "2") (pinfunction "2_2") (pintype "passive"))
      (node (ref "S26") (pin "2") (pinfunction "2_2") (pintype "passive"))
      (node (ref "S43") (pin "2") (pinfunction "2_2") (pintype "passive"))
      (node (ref "S58") (pin "2") (pinfunction "2_2") (pintype "passive"))
      (node (ref "S72") (pin "2") (pinfunction "2_2") (pintype "passive"))
      (node (ref "U1") (pin "18") (pinfunction "P0.14_18") (pintype "passive"))
    )
    (net (code "13") (name "/Col 10") (class "Default")
      (node (ref "S11") (pin "2") (pinfunction "2_2") (pintype "passive"))
      (node (ref "S27") (pin "2") (pinfunction "2_2") (pintype "passive"))
      (node (ref "S44") (pin "2") (pinfunction "2_2") (pintype "passive"))
      (node (ref "S59") (pin "2") (pinfunction "2_2") (pintype "passive"))
      (node (ref "U1") (pin "19") (pinfunction "P0.15_19") (pintype "passive"))
    )
    (net (code "14") (name "/Col 11") (class "Default")
      (node (ref "S12") (pin "2") (pinfunction "2_2") (pintype "passive"))
      (node (ref "S28") (pin "2") (pinfunction "2_2") (pintype "passive"))
      (node (ref "S45") (pin "2") (pinfunction "2_2") (pintype "passive"))
      (node (ref "S60") (pin "2") (pinfunction "2_2") (pintype "passive"))
      (node (ref "U1") (pin "20") (pinfunction "P0.17_20") (pintype "passive"))
    )
    (net (code "15") (name "/Col 12") (class "Default")
      (node (ref "S13") (pin "2") (pinfunction "2_2") (pintype "passive"))
      (node (ref "S29") (pin "2") (pinfunction "2_2") (pintype "passive"))
      (node (ref "S46") (pin "2") (pinfunction "2_2") (pintype "passive"))
      (node (ref "S61") (pin "2") (pinfunction "2_2") (pintype "passive"))
      (node (ref "S73") (pin "2") (pinfunction "2_2") (pintype "passive"))
      (node (ref "U1") (pin "21") (pinfunction "P0.18_21") (pintype "passive"))
    )
    (net (code "16") (name "/Col 13") (class "Default")
      (node (ref "S14") (pin "2") (pinfunction "2_2") (pintype "passive"))
      (node (ref "S30") (pin "2") (pinfunction "2_2") (pintype "passive"))
      (node (ref "S47") (pin "2") (pinfunction "2_2") (pintype "passive"))
      (node (ref "S62") (pin "2") (pinfunction "2_2") (pintype "passive"))
      (node (ref "S74") (pin "2") (pinfunction "2_2") (pintype "passive"))
      (node (ref "U1") (pin "22") (pinfunction "P0.20_22") (pintype "passive"))
    )
    (net (code "17") (name "/Col 14") (class "Default")
      (node (ref "S15") (pin "2") (pinfunction "2_2") (pintype "passive"))
      (node (ref "S31") (pin "2") (pinfunction "2_2") (pintype "passive"))
      (node (ref "S48") (pin "2") (pinfunction "2_2") (pintype "passive"))
      (node (ref "S63") (pin "2") (pinfunction "2_2") (pintype "passive"))
      (node (ref "S75") (pin "2") (pinfunction "2_2") (pintype "passive"))
      (node (ref "U1") (pin "23") (pinfunction "P1.05_23") (pintype "passive"))
    )
    (net (code "18") (name "/Col 15") (class "Default")
      (node (ref "S32") (pin "2") (pinfunction "2_2") (pintype "passive"))
      (node (ref "S64") (pin "2") (pinfunction "2_2") (pintype "passive"))
      (node (ref "S76") (pin "2") (pinfunction "2_2") (pintype "passive"))
      (node (ref "U1") (pin "24") (pinfunction "P1.07_24") (pintype "passive"))
    )
    (net (code "19") (name "/Col 16") (class "Default")
      (node (ref "S16") (pin "2") (pinfunction "2_2") (pintype "passive"))
      (node (ref "S33") (pin "2") (pinfunction "2_2") (pintype "passive"))
      (node (ref "S49") (pin "2") (pinfunction "2_2") (pintype "passive"))
      (node (ref "S65") (pin "2") (pinfunction "2_2") (pintype "passive"))
      (node (ref "S77") (pin "2") (pinfunction "2_2") (pintype "passive"))
      (node (ref "U1") (pin "25") (pinfunction "P1.09_25") (pintype "passive"))
    )
    (net (code "20") (name "/Col 17") (class "Default")
      (node (ref "S17") (pin "2") (pinfunction "2_2") (pintype "passive"))
      (node (ref "S34") (pin "2") (pinfunction "2_2") (pintype "passive"))
      (node (ref "S50") (pin "2") (pinfunction "2_2") (pintype "passive"))
      (node (ref "S66") (pin "2") (pinfunction "2_2") (pintype "passive"))
      (node (ref "S78") (pin "2") (pinfunction "2_2") (pintype "passive"))
      (node (ref "U1") (pin "26") (pinfunction "P0.25_26") (pintype "passive"))
    )
    (net (code "21") (name "/D_N") (class "Default")
      (node (ref "D0") (pin "3") (pinfunction "I/O_2_3") (pintype "bidirectional"))
      (node (ref "J2") (pin "4") (pinfunction "4_4") (pintype "passive"))
      (node (ref "U1") (pin "44") (pinfunction "D-_44") (pintype "passive"))
    )
    (net (code "22") (name "/D_P") (class "Default")
      (node (ref "D0") (pin "2") (pinfunction "I/O_1_2") (pintype "bidirectional"))
      (node (ref "J2") (pin "5") (pinfunction "5_5") (pintype "passive"))
      (node (ref "U1") (pin "45") (pinfunction "D+_45") (pintype "passive"))
    )
    (net (code "23") (name "/GPIO0") (class "Default")
      (node (ref "U2") (pin "7") (pinfunction "GPIO0_7") (pintype "bidirectional"))
    )
    (net (code "24") (name "/GPIO1") (class "Default")
      (node (ref "U2") (pin "8") (pinfunction "GPIO1_8") (pintype "bidirectional"))
    )
    (net (code "25") (name "/GPIO2") (class "Default")
      (node (ref "U2") (pin "9") (pinfunction "GPIO2_9") (pintype "bidirectional"))
    )
    (net (code "26") (name "/GPIO3") (class "Default")
      (node (ref "U2") (pin "10") (pinfunction "GPIO3_10") (pintype "bidirectional"))
    )
    (net (code "27") (name "/GPIO4") (class "Default")
      (node (ref "U2") (pin "11") (pinfunction "GPIO4_11") (pintype "bidirectional"))
    )
    (net (code "28") (name "/LED0") (class "Default")
      (node (ref "G") (pin "2") (pinfunction "2_2") (pintype "passive"))
      (node (ref "U2") (pin "25") (pinfunction "LED0_25") (pintype "output"))
    )
    (net (code "29") (name "/LED1") (class "Default")
      (node (ref "R") (pin "2") (pinfunction "2_2") (pintype "passive"))
      (node (ref "U2") (pin "26") (pinfunction "LED1_26") (pintype "output"))
    )
    (net (code "30") (name "/LED2") (class "Default")
      (node (ref "B") (pin "2") (pinfunction "2_2") (pintype "passive"))
      (node (ref "U2") (pin "27") (pinfunction "LED2_27") (pintype "output"))
    )
    (net (code "31") (name "/LED_MOSI") (class "Default")
      (node (ref "LED1") (pin "6") (pinfunction "DI_6") (pintype "input"))
      (node (ref "U1") (pin "50") (pinfunction "P0.09_50") (pintype "passive"))
    )
    (net (code "32") (name "/LED_MOSI2") (class "Default")
      (node (ref "LED1") (pin "4") (pinfunction "DO_4") (pintype "output"))
      (node (ref "LED3") (pin "6") (pinfunction "DI_6") (pintype "input"))
    )
    (net (code "33") (name "/LED_MOSI3") (class "Default")
      (node (ref "LED3") (pin "4") (pinfunction "DO_4") (pintype "output"))
      (node (ref "LED5") (pin "6") (pinfunction "DI_6") (pintype "input"))
    )
    (net (code "34") (name "/LED_MOSI4") (class "Default")
      (node (ref "LED5") (pin "4") (pinfunction "DO_4") (pintype "output"))
      (node (ref "LED7") (pin "6") (pinfunction "DI_6") (pintype "input"))
    )
    (net (code "35") (name "/LED_MOSI5") (class "Default")
      (node (ref "LED2") (pin "6") (pinfunction "DI_6") (pintype "input"))
      (node (ref "LED7") (pin "4") (pinfunction "DO_4") (pintype "output"))
    )
    (net (code "36") (name "/LED_MOSI6") (class "Default")
      (node (ref "LED2") (pin "4") (pinfunction "DO_4") (pintype "output"))
      (node (ref "LED4") (pin "6") (pinfunction "DI_6") (pintype "input"))
    )
    (net (code "37") (name "/LED_MOSI7") (class "Default")
      (node (ref "LED4") (pin "4") (pinfunction "DO_4") (pintype "output"))
      (node (ref "LED6") (pin "6") (pinfunction "DI_6") (pintype "input"))
    )
    (net (code "38") (name "/LED_MOSI8") (class "Default")
      (node (ref "LED6") (pin "4") (pinfunction "DO_4") (pintype "output"))
      (node (ref "LED8") (pin "6") (pinfunction "DI_6") (pintype "input"))
    )
    (net (code "39") (name "/LED_SCK") (class "Default")
      (node (ref "LED1") (pin "3") (pinfunction "CI_3") (pintype "input"))
      (node (ref "U1") (pin "2") (pinfunction "P0.08_2") (pintype "passive"))
    )
    (net (code "40") (name "/LED_SCK2") (class "Default")
      (node (ref "LED1") (pin "1") (pinfunction "CO_1") (pintype "output"))
      (node (ref "LED3") (pin "3") (pinfunction "CI_3") (pintype "input"))
    )
    (net (code "41") (name "/LED_SCK3") (class "Default")
      (node (ref "LED3") (pin "1") (pinfunction "CO_1") (pintype "output"))
      (node (ref "LED5") (pin "3") (pinfunction "CI_3") (pintype "input"))
    )
    (net (code "42") (name "/LED_SCK4") (class "Default")
      (node (ref "LED5") (pin "1") (pinfunction "CO_1") (pintype "output"))
      (node (ref "LED7") (pin "3") (pinfunction "CI_3") (pintype "input"))
    )
    (net (code "43") (name "/LED_SCK5") (class "Default")
      (node (ref "LED2") (pin "3") (pinfunction "CI_3") (pintype "input"))
      (node (ref "LED7") (pin "1") (pinfunction "CO_1") (pintype "output"))
    )
    (net (code "44") (name "/LED_SCK6") (class "Default")
      (node (ref "LED2") (pin "1") (pinfunction "CO_1") (pintype "output"))
      (node (ref "LED4") (pin "3") (pinfunction "CI_3") (pintype "input"))
    )
    (net (code "45") (name "/LED_SCK7") (class "Default")
      (node (ref "LED4") (pin "1") (pinfunction "CO_1") (pintype "output"))
      (node (ref "LED6") (pin "3") (pinfunction "CI_3") (pintype "input"))
    )
    (net (code "46") (name "/LED_SCK8") (class "Default")
      (node (ref "LED6") (pin "1") (pinfunction "CO_1") (pintype "output"))
      (node (ref "LED8") (pin "3") (pinfunction "CI_3") (pintype "input"))
    )
    (net (code "47") (name "/RESET") (class "Default")
      (node (ref "J3") (pin "5") (pinfunction "5_5") (pintype "passive"))
      (node (ref "U1") (pin "32") (pinfunction "RESET_32") (pintype "passive"))
    )
    (net (code "48") (name "/Row 0") (class "Default")
      (node (ref "D1") (pin "1") (pinfunction "K_1") (pintype "passive"))
      (node (ref "D10") (pin "1") (pinfunction "K_1") (pintype "passive"))
      (node (ref "D11") (pin "1") (pinfunction "K_1") (pintype "passive"))
      (node (ref "D12") (pin "1") (pinfunction "K_1") (pintype "passive"))
      (node (ref "D13") (pin "1") (pinfunction "K_1") (pintype "passive"))
      (node (ref "D14") (pin "1") (pinfunction "K_1") (pintype "passive"))
      (node (ref "D15") (pin "1") (pinfunction "K_1") (pintype "passive"))
      (node (ref "D16") (pin "1") (pinfunction "K_1") (pintype "passive"))
      (node (ref "D17") (pin "1") (pinfunction "K_1") (pintype "passive"))
      (node (ref "D2") (pin "1") (pinfunction "K_1") (pintype "passive"))
      (node (ref "D3") (pin "1") (pinfunction "K_1") (pintype "passive"))
      (node (ref "D4") (pin "1") (pinfunction "K_1") (pintype "passive"))
      (node (ref "D5") (pin "1") (pinfunction "K_1") (pintype "passive"))
      (node (ref "D6") (pin "1") (pinfunction "K_1") (pintype "passive"))
      (node (ref "D7") (pin "1") (pinfunction "K_1") (pintype "passive"))
      (node (ref "D8") (pin "1") (pinfunction "K_1") (pintype "passive"))
      (node (ref "D9") (pin "1") (pinfunction "K_1") (pintype "passive"))
      (node (ref "U1") (pin "27") (pinfunction "P0.29_27") (pintype "passive"))
    )
    (net (code "49") (name "/Row 1") (class "Default")
      (node (ref "D18") (pin "1") (pinfunction "K_1") (pintype "passive"))
      (node (ref "D19") (pin "1") (pinfunction "K_1") (pintype "passive"))
      (node (ref "D20") (pin "1") (pinfunction "K_1") (pintype "passive"))
      (node (ref "D21") (pin "1") (pinfunction "K_1") (pintype "passive"))
      (node (ref "D22") (pin "1") (pinfunction "K_1") (pintype "passive"))
      (node (ref "D23") (pin "1") (pinfunction "K_1") (pintype "passive"))
      (node (ref "D24") (pin "1") (pinfunction "K_1") (pintype "passive"))
      (node (ref "D25") (pin "1") (pinfunction "K_1") (pintype "passive"))
      (node (ref "D26") (pin "1") (pinfunction "K_1") (pintype "passive"))
      (node (ref "D27") (pin "1") (pinfunction "K_1") (pintype "passive"))
      (node (ref "D28") (pin "1") (pinfunction "K_1") (pintype "passive"))
      (node (ref "D29") (pin "1") (pinfunction "K_1") (pintype "passive"))
      (node (ref "D30") (pin "1") (pinfunction "K_1") (pintype "passive"))
      (node (ref "D31") (pin "1") (pinfunction "K_1") (pintype "passive"))
      (node (ref "D32") (pin "1") (pinfunction "K_1") (pintype "passive"))
      (node (ref "D33") (pin "1") (pinfunction "K_1") (pintype "passive"))
      (node (ref "D34") (pin "1") (pinfunction "K_1") (pintype "passive"))
      (node (ref "U1") (pin "28") (pinfunction "P0.19_28") (pintype "passive"))
    )
    (net (code "50") (name "/Row 2") (class "Default")
      (node (ref "D35") (pin "1") (pinfunction "K_1") (pintype "passive"))
      (node (ref "D36") (pin "1") (pinfunction "K_1") (pintype "passive"))
      (node (ref "D37") (pin "1") (pinfunction "K_1") (pintype "passive"))
      (node (ref "D38") (pin "1") (pinfunction "K_1") (pintype "passive"))
      (node (ref "D39") (pin "1") (pinfunction "K_1") (pintype "passive"))
      (node (ref "D40") (pin "1") (pinfunction "K_1") (pintype "passive"))
      (node (ref "D41") (pin "1") (pinfunction "K_1") (pintype "passive"))
      (node (ref "D42") (pin "1") (pinfunction "K_1") (pintype "passive"))
      (node (ref "D43") (pin "1") (pinfunction "K_1") (pintype "passive"))
      (node (ref "D44") (pin "1") (pinfunction "K_1") (pintype "passive"))
      (node (ref "D45") (pin "1") (pinfunction "K_1") (pintype "passive"))
      (node (ref "D46") (pin "1") (pinfunction "K_1") (pintype "passive"))
      (node (ref "D47") (pin "1") (pinfunction "K_1") (pintype "passive"))
      (node (ref "D48") (pin "1") (pinfunction "K_1") (pintype "passive"))
      (node (ref "D49") (pin "1") (pinfunction "K_1") (pintype "passive"))
      (node (ref "D50") (pin "1") (pinfunction "K_1") (pintype "passive"))
      (node (ref "U1") (pin "29") (pinfunction "P0.21_29") (pintype "passive"))
    )
    (net (code "51") (name "/Row 3") (class "Default")
      (node (ref "D51") (pin "1") (pinfunction "K_1") (pintype "passive"))
      (node (ref "D52") (pin "1") (pinfunction "K_1") (pintype "passive"))
      (node (ref "D53") (pin "1") (pinfunction "K_1") (pintype "passive"))
      (node (ref "D54") (pin "1") (pinfunction "K_1") (pintype "passive"))
      (node (ref "D55") (pin "1") (pinfunction "K_1") (pintype "passive"))
      (node (ref "D56") (pin "1") (pinfunction "K_1") (pintype "passive"))
      (node (ref "D57") (pin "1") (pinfunction "K_1") (pintype "passive"))
      (node (ref "D58") (pin "1") (pinfunction "K_1") (pintype "passive"))
      (node (ref "D59") (pin "1") (pinfunction "K_1") (pintype "passive"))
      (node (ref "D60") (pin "1") (pinfunction "K_1") (pintype "passive"))
      (node (ref "D61") (pin "1") (pinfunction "K_1") (pintype "passive"))
      (node (ref "D62") (pin "1") (pinfunction "K_1") (pintype "passive"))
      (node (ref "D63") (pin "1") (pinfunction "K_1") (pintype "passive"))
      (node (ref "D64") (pin "1") (pinfunction "K_1") (pintype "passive"))
      (node (ref "D65") (pin "1") (pinfunction "K_1") (pintype "passive"))
      (node (ref "D66") (pin "1") (pinfunction "K_1") (pintype "passive"))
      (node (ref "U1") (pin "48") (pinfunction "P0.23_48") (pintype "passive"))
    )
    (net (code "52") (name "/Row 4") (class "Default")
      (node (ref "D67") (pin "1") (pinfunction "K_1") (pintype "passive"))
      (node (ref "D68") (pin "1") (pinfunction "K_1") (pintype "passive"))
      (node (ref "D69") (pin "1") (pinfunction "K_1") (pintype "passive"))
      (node (ref "D70") (pin "1") (pinfunction "K_1") (pintype "passive"))
      (node (ref "D71") (pin "1") (pinfunction "K_1") (pintype "passive"))
      (node (ref "D72") (pin "1") (pinfunction "K_1") (pintype "passive"))
      (node (ref "D73") (pin "1") (pinfunction "K_1") (pintype "passive"))
      (node (ref "D74") (pin "1") (pinfunction "K_1") (pintype "passive"))
      (node (ref "D75") (pin "1") (pinfunction "K_1") (pintype "passive"))
      (node (ref "D76") (pin "1") (pinfunction "K_1") (pintype "passive"))
      (node (ref "D77") (pin "1") (pinfunction "K_1") (pintype "passive"))
      (node (ref "D78") (pin "1") (pinfunction "K_1") (pintype "passive"))
      (node (ref "U1") (pin "49") (pinfunction "P0.22_49") (pintype "passive"))
    )
    (net (code "53") (name "/SCL") (class "Default")
      (node (ref "U1") (pin "30") (pinfunction "P1.06_30") (pintype "passive"))
      (node (ref "U2") (pin "14") (pinfunction "SCL_14") (pintype "input"))
    )
    (net (code "54") (name "/SDA") (class "Default")
      (node (ref "U1") (pin "31") (pinfunction "P0.27_31") (pintype "passive"))
      (node (ref "U2") (pin "13") (pinfunction "SDA_13") (pintype "open_collector"))
    )
    (net (code "55") (name "/SHPHLD") (class "Default")
      (node (ref "U2") (pin "15") (pinfunction "SHPHLD_15") (pintype "input"))
    )
    (net (code "56") (name "/SW1") (class "Default")
      (node (ref "L1") (pin "2") (pinfunction "2_2") (pintype "passive"))
      (node (ref "U2") (pin "3") (pinfunction "SW1_3") (pintype "power_in"))
    )
    (net (code "57") (name "/SWDCLK") (class "Default")
      (node (ref "J3") (pin "1") (pinfunction "1_1") (pintype "passive"))
      (node (ref "U1") (pin "36") (pinfunction "SWDCLK_36") (pintype "passive"))
    )
    (net (code "58") (name "/SWDIO") (class "Default")
      (node (ref "J3") (pin "3") (pinfunction "3_3") (pintype "passive"))
      (node (ref "U1") (pin "35") (pinfunction "SWDIO_35") (pintype "passive"))
    )
    (net (code "59") (name "/VSET1") (class "Default")
      (node (ref "R1") (pin "2") (pinfunction "2_2") (pintype "passive"))
      (node (ref "U2") (pin "17") (pinfunction "VSET1_17") (pintype "input"))
    )
    (net (code "60") (name "GND") (class "Default")
      (node (ref "C1") (pin "1") (pinfunction "1_1") (pintype "passive"))
      (node (ref "C10") (pin "1") (pinfunction "1_1") (pintype "passive"))
      (node (ref "C11") (pin "1") (pinfunction "1_1") (pintype "passive"))
      (node (ref "C12") (pin "1") (pinfunction "1_1") (pintype "passive"))
      (node (ref "C13") (pin "1") (pinfunction "1_1") (pintype "passive"))
      (node (ref "C14") (pin "1") (pinfunction "1_1") (pintype "passive"))
      (node (ref "C2") (pin "1") (pinfunction "1_1") (pintype "passive"))
      (node (ref "C4") (pin "1") (pinfunction "1_1") (pintype "passive"))
      (node (ref "C5") (pin "1") (pinfunction "1_1") (pintype "passive"))
      (node (ref "C6") (pin "1") (pinfunction "1_1") (pintype "passive"))
      (node (ref "C7") (pin "1") (pinfunction "1_1") (pintype "passive"))
      (node (ref "C9") (pin "2") (pinfunction "2_2") (pintype "passive"))
      (node (ref "D0") (pin "4") (pinfunction "VCC_4") (pintype "power_in"))
      (node (ref "J1") (pin "2") (pinfunction "2_2") (pintype "passive"))
      (node (ref "J2") (pin "2") (pinfunction "2_2") (pintype "passive"))
      (node (ref "J3") (pin "4") (pinfunction "4_4") (pintype "passive"))
      (node (ref "LED1") (pin "5_1") (pinfunction "GND_5_1") (pintype "power_in"))
      (node (ref "LED1") (pin "5_2") (pinfunction "GND_5_2") (pintype "power_in"))
      (node (ref "LED2") (pin "5_1") (pinfunction "GND_5_1") (pintype "power_in"))
      (node (ref "LED2") (pin "5_2") (pinfunction "GND_5_2") (pintype "power_in"))
      (node (ref "LED3") (pin "5_1") (pinfunction "GND_5_1") (pintype "power_in"))
      (node (ref "LED3") (pin "5_2") (pinfunction "GND_5_2") (pintype "power_in"))
      (node (ref "LED4") (pin "5_1") (pinfunction "GND_5_1") (pintype "power_in"))
      (node (ref "LED4") (pin "5_2") (pinfunction "GND_5_2") (pintype "power_in"))
      (node (ref "LED5") (pin "5_1") (pinfunction "GND_5_1") (pintype "power_in"))
      (node (ref "LED5") (pin "5_2") (pinfunction "GND_5_2") (pintype "power_in"))
      (node (ref "LED6") (pin "5_1") (pinfunction "GND_5_1") (pintype "power_in"))
      (node (ref "LED6") (pin "5_2") (pinfunction "GND_5_2") (pintype "power_in"))
      (node (ref "LED7") (pin "5_1") (pinfunction "GND_5_1") (pintype "power_in"))
      (node (ref "LED7") (pin "5_2") (pinfunction "GND_5_2") (pintype "power_in"))
      (node (ref "LED8") (pin "5_1") (pinfunction "GND_5_1") (pintype "power_in"))
      (node (ref "LED8") (pin "5_2") (pinfunction "GND_5_2") (pintype "power_in"))
      (node (ref "R1") (pin "1") (pinfunction "1_1") (pintype "passive"))
      (node (ref "U1") (pin "1") (pinfunction "GND_1") (pintype "passive"))
      (node (ref "U1") (pin "11") (pinfunction "GND_11") (pintype "passive"))
      (node (ref "U1") (pin "12") (pinfunction "GND_12") (pintype "passive"))
      (node (ref "U2") (pin "18") (pinfunction "NTC_18") (pintype "input"))
      (node (ref "U2") (pin "2") (pinfunction "PVSS1_2") (pintype "power_in"))
      (node (ref "U2") (pin "28") (pinfunction "LSIN1/VINLDO1_28") (pintype "power_in"))
      (node (ref "U2") (pin "29") (pinfunction "LSOUT1/VOUTLDO1_29") (pintype "power_in"))
      (node (ref "U2") (pin "30") (pinfunction "LSIN2/VINLDO2_30") (pintype "power_in"))
      (node (ref "U2") (pin "31") (pinfunction "LSOUT2/VOUTLDO2_31") (pintype "power_in"))
      (node (ref "U2") (pin "33") (pinfunction "AVSS_33") (pintype "power_in"))
      (node (ref "U2") (pin "6") (pinfunction "PVSS2_6") (pintype "power_in"))
    )
    (net (code "61") (name "Net-(D1-A)") (class "Default")
      (node (ref "D1") (pin "2") (pinfunction "A_2") (pintype "passive"))
      (node (ref "S1") (pin "1") (pinfunction "1_1") (pintype "passive"))
    )
    (net (code "62") (name "Net-(D2-A)") (class "Default")
      (node (ref "D2") (pin "2") (pinfunction "A_2") (pintype "passive"))
      (node (ref "S2") (pin "1") (pinfunction "1_1") (pintype "passive"))
    )
    (net (code "63") (name "Net-(D3-A)") (class "Default")
      (node (ref "D3") (pin "2") (pinfunction "A_2") (pintype "passive"))
      (node (ref "S3") (pin "1") (pinfunction "1_1") (pintype "passive"))
    )
    (net (code "64") (name "Net-(D4-A)") (class "Default")
      (node (ref "D4") (pin "2") (pinfunction "A_2") (pintype "passive"))
      (node (ref "S4") (pin "1") (pinfunction "1_1") (pintype "passive"))
    )
    (net (code "65") (name "Net-(D5-A)") (class "Default")
      (node (ref "D5") (pin "2") (pinfunction "A_2") (pintype "passive"))
      (node (ref "S5") (pin "1") (pinfunction "1_1") (pintype "passive"))
    )
    (net (code "66") (name "Net-(D6-A)") (class "Default")
      (node (ref "D6") (pin "2") (pinfunction "A_2") (pintype "passive"))
      (node (ref "S6") (pin "1") (pinfunction "1_1") (pintype "passive"))
    )
    (net (code "67") (name "Net-(D7-A)") (class "Default")
      (node (ref "D7") (pin "2") (pinfunction "A_2") (pintype "passive"))
      (node (ref "S7") (pin "1") (pinfunction "1_1") (pintype "passive"))
    )
    (net (code "68") (name "Net-(D8-A)") (class "Default")
      (node (ref "D8") (pin "2") (pinfunction "A_2") (pintype "passive"))
      (node (ref "S8") (pin "1") (pinfunction "1_1") (pintype "passive"))
    )
    (net (code "69") (name "Net-(D9-A)") (class "Default")
      (node (ref "D9") (pin "2") (pinfunction "A_2") (pintype "passive"))
      (node (ref "S9") (pin "1") (pinfunction "1_1") (pintype "passive"))
    )
    (net (code "70") (name "Net-(D10-A)") (class "Default")
      (node (ref "D10") (pin "2") (pinfunction "A_2") (pintype "passive"))
      (node (ref "S10") (pin "1") (pinfunction "1_1") (pintype "passive"))
    )
    (net (code "71") (name "Net-(D11-A)") (class "Default")
      (node (ref "D11") (pin "2") (pinfunction "A_2") (pintype "passive"))
      (node (ref "S11") (pin "1") (pinfunction "1_1") (pintype "passive"))
    )
    (net (code "72") (name "Net-(D12-A)") (class "Default")
      (node (ref "D12") (pin "2") (pinfunction "A_2") (pintype "passive"))
      (node (ref "S12") (pin "1") (pinfunction "1_1") (pintype "passive"))
    )
    (net (code "73") (name "Net-(D13-A)") (class "Default")
      (node (ref "D13") (pin "2") (pinfunction "A_2") (pintype "passive"))
      (node (ref "S13") (pin "1") (pinfunction "1_1") (pintype "passive"))
    )
    (net (code "74") (name "Net-(D14-A)") (class "Default")
      (node (ref "D14") (pin "2") (pinfunction "A_2") (pintype "passive"))
      (node (ref "S14") (pin "1") (pinfunction "1_1") (pintype "passive"))
    )
    (net (code "75") (name "Net-(D15-A)") (class "Default")
      (node (ref "D15") (pin "2") (pinfunction "A_2") (pintype "passive"))
      (node (ref "S15") (pin "1") (pinfunction "1_1") (pintype "passive"))
    )
    (net (code "76") (name "Net-(D16-A)") (class "Default")
      (node (ref "D16") (pin "2") (pinfunction "A_2") (pintype "passive"))
      (node (ref "S16") (pin "1") (pinfunction "1_1") (pintype "passive"))
    )
    (net (code "77") (name "Net-(D17-A)") (class "Default")
      (node (ref "D17") (pin "2") (pinfunction "A_2") (pintype "passive"))
      (node (ref "S17") (pin "1") (pinfunction "1_1") (pintype "passive"))
    )
    (net (code "78") (name "Net-(D18-A)") (class "Default")
      (node (ref "D18") (pin "2") (pinfunction "A_2") (pintype "passive"))
      (node (ref "S18") (pin "1") (pinfunction "1_1") (pintype "passive"))
    )
    (net (code "79") (name "Net-(D19-A)") (class "Default")
      (node (ref "D19") (pin "2") (pinfunction "A_2") (pintype "passive"))
      (node (ref "S19") (pin "1") (pinfunction "1_1") (pintype "passive"))
    )
    (net (code "80") (name "Net-(D20-A)") (class "Default")
      (node (ref "D20") (pin "2") (pinfunction "A_2") (pintype "passive"))
      (node (ref "S20") (pin "1") (pinfunction "1_1") (pintype "passive"))
    )
    (net (code "81") (name "Net-(D21-A)") (class "Default")
      (node (ref "D21") (pin "2") (pinfunction "A_2") (pintype "passive"))
      (node (ref "S21") (pin "1") (pinfunction "1_1") (pintype "passive"))
    )
    (net (code "82") (name "Net-(D22-A)") (class "Default")
      (node (ref "D22") (pin "2") (pinfunction "A_2") (pintype "passive"))
      (node (ref "S22") (pin "1") (pinfunction "1_1") (pintype "passive"))
    )
    (net (code "83") (name "Net-(D23-A)") (class "Default")
      (node (ref "D23") (pin "2") (pinfunction "A_2") (pintype "passive"))
      (node (ref "S23") (pin "1") (pinfunction "1_1") (pintype "passive"))
    )
    (net (code "84") (name "Net-(D24-A)") (class "Default")
      (node (ref "D24") (pin "2") (pinfunction "A_2") (pintype "passive"))
      (node (ref "S24") (pin "1") (pinfunction "1_1") (pintype "passive"))
    )
    (net (code "85") (name "Net-(D25-A)") (class "Default")
      (node (ref "D25") (pin "2") (pinfunction "A_2") (pintype "passive"))
      (node (ref "S25") (pin "1") (pinfunction "1_1") (pintype "passive"))
    )
    (net (code "86") (name "Net-(D26-A)") (class "Default")
      (node (ref "D26") (pin "2") (pinfunction "A_2") (pintype "passive"))
      (node (ref "S26") (pin "1") (pinfunction "1_1") (pintype "passive"))
    )
    (net (code "87") (name "Net-(D27-A)") (class "Default")
      (node (ref "D27") (pin "2") (pinfunction "A_2") (pintype "passive"))
      (node (ref "S27") (pin "1") (pinfunction "1_1") (pintype "passive"))
    )
    (net (code "88") (name "Net-(D28-A)") (class "Default")
      (node (ref "D28") (pin "2") (pinfunction "A_2") (pintype "passive"))
      (node (ref "S28") (pin "1") (pinfunction "1_1") (pintype "passive"))
    )
    (net (code "89") (name "Net-(D29-A)") (class "Default")
      (node (ref "D29") (pin "2") (pinfunction "A_2") (pintype "passive"))
      (node (ref "S29") (pin "1") (pinfunction "1_1") (pintype "passive"))
    )
    (net (code "90") (name "Net-(D30-A)") (class "Default")
      (node (ref "D30") (pin "2") (pinfunction "A_2") (pintype "passive"))
      (node (ref "S30") (pin "1") (pinfunction "1_1") (pintype "passive"))
    )
    (net (code "91") (name "Net-(D31-A)") (class "Default")
      (node (ref "D31") (pin "2") (pinfunction "A_2") (pintype "passive"))
      (node (ref "S31") (pin "1") (pinfunction "1_1") (pintype "passive"))
    )
    (net (code "92") (name "Net-(D32-A)") (class "Default")
      (node (ref "D32") (pin "2") (pinfunction "A_2") (pintype "passive"))
      (node (ref "S32") (pin "1") (pinfunction "1_1") (pintype "passive"))
    )
    (net (code "93") (name "Net-(D33-A)") (class "Default")
      (node (ref "D33") (pin "2") (pinfunction "A_2") (pintype "passive"))
      (node (ref "S33") (pin "1") (pinfunction "1_1") (pintype "passive"))
    )
    (net (code "94") (name "Net-(D34-A)") (class "Default")
      (node (ref "D34") (pin "2") (pinfunction "A_2") (pintype "passive"))
      (node (ref "S34") (pin "1") (pinfunction "1_1") (pintype "passive"))
    )
    (net (code "95") (name "Net-(D35-A)") (class "Default")
      (node (ref "D35") (pin "2") (pinfunction "A_2") (pintype "passive"))
      (node (ref "S35") (pin "1") (pinfunction "1_1") (pintype "passive"))
    )
    (net (code "96") (name "Net-(D36-A)") (class "Default")
      (node (ref "D36") (pin "2") (pinfunction "A_2") (pintype "passive"))
      (node (ref "S36") (pin "1") (pinfunction "1_1") (pintype "passive"))
    )
    (net (code "97") (name "Net-(D37-A)") (class "Default")
      (node (ref "D37") (pin "2") (pinfunction "A_2") (pintype "passive"))
      (node (ref "S37") (pin "1") (pinfunction "1_1") (pintype "passive"))
    )
    (net (code "98") (name "Net-(D38-A)") (class "Default")
      (node (ref "D38") (pin "2") (pinfunction "A_2") (pintype "passive"))
      (node (ref "S38") (pin "1") (pinfunction "1_1") (pintype "passive"))
    )
    (net (code "99") (name "Net-(D39-A)") (class "Default")
      (node (ref "D39") (pin "2") (pinfunction "A_2") (pintype "passive"))
      (node (ref "S39") (pin "1") (pinfunction "1_1") (pintype "passive"))
    )
    (net (code "100") (name "Net-(D40-A)") (class "Default")
      (node (ref "D40") (pin "2") (pinfunction "A_2") (pintype "passive"))
      (node (ref "S40") (pin "1") (pinfunction "1_1") (pintype "passive"))
    )
    (net (code "101") (name "Net-(D41-A)") (class "Default")
      (node (ref "D41") (pin "2") (pinfunction "A_2") (pintype "passive"))
      (node (ref "S41") (pin "1") (pinfunction "1_1") (pintype "passive"))
    )
    (net (code "102") (name "Net-(D42-A)") (class "Default")
      (node (ref "D42") (pin "2") (pinfunction "A_2") (pintype "passive"))
      (node (ref "S42") (pin "1") (pinfunction "1_1") (pintype "passive"))
    )
    (net (code "103") (name "Net-(D43-A)") (class "Default")
      (node (ref "D43") (pin "2") (pinfunction "A_2") (pintype "passive"))
      (node (ref "S43") (pin "1") (pinfunction "1_1") (pintype "passive"))
    )
    (net (code "104") (name "Net-(D44-A)") (class "Default")
      (node (ref "D44") (pin "2") (pinfunction "A_2") (pintype "passive"))
      (node (ref "S44") (pin "1") (pinfunction "1_1") (pintype "passive"))
    )
    (net (code "105") (name "Net-(D45-A)") (class "Default")
      (node (ref "D45") (pin "2") (pinfunction "A_2") (pintype "passive"))
      (node (ref "S45") (pin "1") (pinfunction "1_1") (pintype "passive"))
    )
    (net (code "106") (name "Net-(D46-A)") (class "Default")
      (node (ref "D46") (pin "2") (pinfunction "A_2") (pintype "passive"))
      (node (ref "S46") (pin "1") (pinfunction "1_1") (pintype "passive"))
    )
    (net (code "107") (name "Net-(D47-A)") (class "Default")
      (node (ref "D47") (pin "2") (pinfunction "A_2") (pintype "passive"))
      (node (ref "S47") (pin "1") (pinfunction "1_1") (pintype "passive"))
    )
    (net (code "108") (name "Net-(D48-A)") (class "Default")
      (node (ref "D48") (pin "2") (pinfunction "A_2") (pintype "passive"))
      (node (ref "S48") (pin "1") (pinfunction "1_1") (pintype "passive"))
    )
    (net (code "109") (name "Net-(D49-A)") (class "Default")
      (node (ref "D49") (pin "2") (pinfunction "A_2") (pintype "passive"))
      (node (ref "S49") (pin "1") (pinfunction "1_1") (pintype "passive"))
    )
    (net (code "110") (name "Net-(D50-A)") (class "Default")
      (node (ref "D50") (pin "2") (pinfunction "A_2") (pintype "passive"))
      (node (ref "S50") (pin "1") (pinfunction "1_1") (pintype "passive"))
    )
    (net (code "111") (name "Net-(D51-A)") (class "Default")
      (node (ref "D51") (pin "2") (pinfunction "A_2") (pintype "passive"))
      (node (ref "S51") (pin "1") (pinfunction "1_1") (pintype "passive"))
    )
    (net (code "112") (name "Net-(D52-A)") (class "Default")
      (node (ref "D52") (pin "2") (pinfunction "A_2") (pintype "passive"))
      (node (ref "S52") (pin "1") (pinfunction "1_1") (pintype "passive"))
    )
    (net (code "113") (name "Net-(D53-A)") (class "Default")
      (node (ref "D53") (pin "2") (pinfunction "A_2") (pintype "passive"))
      (node (ref "S53") (pin "1") (pinfunction "1_1") (pintype "passive"))
    )
    (net (code "114") (name "Net-(D54-A)") (class "Default")
      (node (ref "D54") (pin "2") (pinfunction "A_2") (pintype "passive"))
      (node (ref "S54") (pin "1") (pinfunction "1_1") (pintype "passive"))
    )
    (net (code "115") (name "Net-(D55-A)") (class "Default")
      (node (ref "D55") (pin "2") (pinfunction "A_2") (pintype "passive"))
      (node (ref "S55") (pin "1") (pinfunction "1_1") (pintype "passive"))
    )
    (net (code "116") (name "Net-(D56-A)") (class "Default")
      (node (ref "D56") (pin "2") (pinfunction "A_2") (pintype "passive"))
      (node (ref "S56") (pin "1") (pinfunction "1_1") (pintype "passive"))
    )
    (net (code "117") (name "Net-(D57-A)") (class "Default")
      (node (ref "D57") (pin "2") (pinfunction "A_2") (pintype "passive"))
      (node (ref "S57") (pin "1") (pinfunction "1_1") (pintype "passive"))
    )
    (net (code "118") (name "Net-(D58-A)") (class "Default")
      (node (ref "D58") (pin "2") (pinfunction "A_2") (pintype "passive"))
      (node (ref "S58") (pin "1") (pinfunction "1_1") (pintype "passive"))
    )
    (net (code "119") (name "Net-(D59-A)") (class "Default")
      (node (ref "D59") (pin "2") (pinfunction "A_2") (pintype "passive"))
      (node (ref "S59") (pin "1") (pinfunction "1_1") (pintype "passive"))
    )
    (net (code "120") (name "Net-(D60-A)") (class "Default")
      (node (ref "D60") (pin "2") (pinfunction "A_2") (pintype "passive"))
      (node (ref "S60") (pin "1") (pinfunction "1_1") (pintype "passive"))
    )
    (net (code "121") (name "Net-(D61-A)") (class "Default")
      (node (ref "D61") (pin "2") (pinfunction "A_2") (pintype "passive"))
      (node (ref "S61") (pin "1") (pinfunction "1_1") (pintype "passive"))
    )
    (net (code "122") (name "Net-(D62-A)") (class "Default")
      (node (ref "D62") (pin "2") (pinfunction "A_2") (pintype "passive"))
      (node (ref "S62") (pin "1") (pinfunction "1_1") (pintype "passive"))
    )
    (net (code "123") (name "Net-(D63-A)") (class "Default")
      (node (ref "D63") (pin "2") (pinfunction "A_2") (pintype "passive"))
      (node (ref "S63") (pin "1") (pinfunction "1_1") (pintype "passive"))
    )
    (net (code "124") (name "Net-(D64-A)") (class "Default")
      (node (ref "D64") (pin "2") (pinfunction "A_2") (pintype "passive"))
      (node (ref "S64") (pin "1") (pinfunction "1_1") (pintype "passive"))
    )
    (net (code "125") (name "Net-(D65-A)") (class "Default")
      (node (ref "D65") (pin "2") (pinfunction "A_2") (pintype "passive"))
      (node (ref "S65") (pin "1") (pinfunction "1_1") (pintype "passive"))
    )
    (net (code "126") (name "Net-(D66-A)") (class "Default")
      (node (ref "D66") (pin "2") (pinfunction "A_2") (pintype "passive"))
      (node (ref "S66") (pin "1") (pinfunction "1_1") (pintype "passive"))
    )
    (net (code "127") (name "Net-(D67-A)") (class "Default")
      (node (ref "D67") (pin "2") (pinfunction "A_2") (pintype "passive"))
      (node (ref "S67") (pin "1") (pinfunction "1_1") (pintype "passive"))
    )
    (net (code "128") (name "Net-(D68-A)") (class "Default")
      (node (ref "D68") (pin "2") (pinfunction "A_2") (pintype "passive"))
      (node (ref "S68") (pin "1") (pinfunction "1_1") (pintype "passive"))
    )
    (net (code "129") (name "Net-(D69-A)") (class "Default")
      (node (ref "D69") (pin "2") (pinfunction "A_2") (pintype "passive"))
      (node (ref "S69") (pin "1") (pinfunction "1_1") (pintype "passive"))
    )
    (net (code "130") (name "Net-(D70-A)") (class "Default")
      (node (ref "D70") (pin "2") (pinfunction "A_2") (pintype "passive"))
      (node (ref "S70") (pin "1") (pinfunction "1_1") (pintype "passive"))
    )
    (net (code "131") (name "Net-(D71-A)") (class "Default")
      (node (ref "D71") (pin "2") (pinfunction "A_2") (pintype "passive"))
      (node (ref "S71") (pin "1") (pinfunction "1_1") (pintype "passive"))
    )
    (net (code "132") (name "Net-(D72-A)") (class "Default")
      (node (ref "D72") (pin "2") (pinfunction "A_2") (pintype "passive"))
      (node (ref "S72") (pin "1") (pinfunction "1_1") (pintype "passive"))
    )
    (net (code "133") (name "Net-(D73-A)") (class "Default")
      (node (ref "D73") (pin "2") (pinfunction "A_2") (pintype "passive"))
      (node (ref "S73") (pin "1") (pinfunction "1_1") (pintype "passive"))
    )
    (net (code "134") (name "Net-(D74-A)") (class "Default")
      (node (ref "D74") (pin "2") (pinfunction "A_2") (pintype "passive"))
      (node (ref "S74") (pin "1") (pinfunction "1_1") (pintype "passive"))
    )
    (net (code "135") (name "Net-(D75-A)") (class "Default")
      (node (ref "D75") (pin "2") (pinfunction "A_2") (pintype "passive"))
      (node (ref "S75") (pin "1") (pinfunction "1_1") (pintype "passive"))
    )
    (net (code "136") (name "Net-(D76-A)") (class "Default")
      (node (ref "D76") (pin "2") (pinfunction "A_2") (pintype "passive"))
      (node (ref "S76") (pin "1") (pinfunction "1_1") (pintype "passive"))
    )
    (net (code "137") (name "Net-(D77-A)") (class "Default")
      (node (ref "D77") (pin "2") (pinfunction "A_2") (pintype "passive"))
      (node (ref "S77") (pin "1") (pinfunction "1_1") (pintype "passive"))
    )
    (net (code "138") (name "Net-(D78-A)") (class "Default")
      (node (ref "D78") (pin "2") (pinfunction "A_2") (pintype "passive"))
      (node (ref "S78") (pin "1") (pinfunction "1_1") (pintype "passive"))
    )
    (net (code "139") (name "VBAT") (class "Default")
      (node (ref "C6") (pin "2") (pinfunction "2_2") (pintype "passive"))
      (node (ref "J1") (pin "1") (pinfunction "1_1") (pintype "passive"))
      (node (ref "U2") (pin "19") (pinfunction "VBAT_19") (pintype "passive"))
    )
    (net (code "140") (name "VBUSIN") (class "Default")
      (node (ref "C1") (pin "2") (pinfunction "2_2") (pintype "passive"))
      (node (ref "C10") (pin "2") (pinfunction "2_2") (pintype "passive"))
      (node (ref "C11") (pin "2") (pinfunction "2_2") (pintype "passive"))
      (node (ref "C13") (pin "2") (pinfunction "2_2") (pintype "passive"))
      (node (ref "C14") (pin "2") (pinfunction "2_2") (pintype "passive"))
      (node (ref "D0") (pin "1") (pinfunction "GND_1") (pintype "power_in"))
      (node (ref "J2") (pin "1") (pinfunction "1_1") (pintype "passive"))
      (node (ref "LED1") (pin "2_1") (pinfunction "VDD_2_1") (pintype "power_in"))
      (node (ref "LED1") (pin "2_2") (pinfunction "VDD_2_2") (pintype "power_in"))
      (node (ref "LED2") (pin "2_1") (pinfunction "VDD_2_1") (pintype "power_in"))
      (node (ref "LED2") (pin "2_2") (pinfunction "VDD_2_2") (pintype "power_in"))
      (node (ref "LED3") (pin "2_1") (pinfunction "VDD_2_1") (pintype "power_in"))
      (node (ref "LED3") (pin "2_2") (pinfunction "VDD_2_2") (pintype "power_in"))
      (node (ref "LED4") (pin "2_1") (pinfunction "VDD_2_1") (pintype "power_in"))
      (node (ref "LED4") (pin "2_2") (pinfunction "VDD_2_2") (pintype "power_in"))
      (node (ref "LED5") (pin "2_1") (pinfunction "VDD_2_1") (pintype "power_in"))
      (node (ref "LED5") (pin "2_2") (pinfunction "VDD_2_2") (pintype "power_in"))
      (node (ref "LED6") (pin "2_1") (pinfunction "VDD_2_1") (pintype "power_in"))
      (node (ref "LED6") (pin "2_2") (pinfunction "VDD_2_2") (pintype "power_in"))
      (node (ref "LED7") (pin "2_1") (pinfunction "VDD_2_1") (pintype "power_in"))
      (node (ref "LED7") (pin "2_2") (pinfunction "VDD_2_2") (pintype "power_in"))
      (node (ref "LED8") (pin "2_1") (pinfunction "VDD_2_1") (pintype "power_in"))
      (node (ref "LED8") (pin "2_2") (pinfunction "VDD_2_2") (pintype "power_in"))
      (node (ref "U2") (pin "21") (pinfunction "VBUS_21") (pintype "power_in"))
    )
    (net (code "141") (name "VBUSOUT") (class "Default")
      (node (ref "C5") (pin "2") (pinfunction "2_2") (pintype "passive"))
      (node (ref "U1") (pin "13") (pinfunction "VBUS_13") (pintype "passive"))
      (node (ref "U2") (pin "22") (pinfunction "VBUSOUT_22") (pintype "power_in"))
    )
    (net (code "142") (name "VOUT1") (class "Default")
      (node (ref "C12") (pin "2") (pinfunction "2_2") (pintype "passive"))
      (node (ref "C7") (pin "2") (pinfunction "2_2") (pintype "passive"))
      (node (ref "C9") (pin "1") (pinfunction "1_1") (pintype "passive"))
      (node (ref "J3") (pin "2") (pinfunction "2_2") (pintype "passive"))
      (node (ref "L1") (pin "1") (pinfunction "1_1") (pintype "passive"))
      (node (ref "U1") (pin "14") (pinfunction "VDDH_14") (pintype "passive"))
      (node (ref "U1") (pin "16") (pinfunction "VDD_16") (pintype "passive"))
      (node (ref "U2") (pin "1") (pinfunction "VOUT1_1") (pintype "power_in"))
      (node (ref "U2") (pin "12") (pinfunction "VDDIO_12") (pintype "power_in"))
    )
    (net (code "143") (name "VSYS") (class "Default")
      (node (ref "B") (pin "1") (pinfunction "1_1") (pintype "passive"))
      (node (ref "C2") (pin "2") (pinfunction "2_2") (pintype "passive"))
      (node (ref "C4") (pin "2") (pinfunction "2_2") (pintype "passive"))
      (node (ref "G") (pin "1") (pinfunction "1_1") (pintype "passive"))
      (node (ref "R") (pin "1") (pinfunction "1_1") (pintype "passive"))
      (node (ref "U2") (pin "20") (pinfunction "VSYS_20") (pintype "power_in"))
      (node (ref "U2") (pin "32") (pinfunction "VOUT2_32") (pintype "power_in"))
      (node (ref "U2") (pin "4") (pinfunction "PVDD_4") (pintype "power_in"))
    )
    (net (code "144") (name "unconnected-(J2-PadMP1)") (class "Default")
      (node (ref "J2") (pin "MP1") (pinfunction "MP1_MP1") (pintype "passive"))
    )
    (net (code "145") (name "unconnected-(J2-PadMP2)") (class "Default")
      (node (ref "J2") (pin "MP2") (pinfunction "MP2_MP2") (pintype "passive"))
    )
    (net (code "146") (name "unconnected-(J3-Pad6)") (class "Default")
      (node (ref "J3") (pin "6") (pinfunction "6_6") (pintype "passive"))
    )
    (net (code "147") (name "unconnected-(LED8-CO-Pad1)") (class "Default")
      (node (ref "LED8") (pin "1") (pinfunction "CO_1") (pintype "output"))
    )
    (net (code "148") (name "unconnected-(LED8-DO-Pad4)") (class "Default")
      (node (ref "LED8") (pin "4") (pinfunction "DO_4") (pintype "output"))
    )
    (net (code "149") (name "unconnected-(U1-DCCH-Pad15)") (class "Default")
      (node (ref "U1") (pin "15") (pinfunction "DCCH_15") (pintype "passive"))
    )
    (net (code "150") (name "unconnected-(U1-P0.02-Pad46)") (class "Default")
      (node (ref "U1") (pin "46") (pinfunction "P0.02_46") (pintype "passive"))
    )
    (net (code "151") (name "unconnected-(U1-P0.03-Pad47)") (class "Default")
      (node (ref "U1") (pin "47") (pinfunction "P0.03_47") (pintype "passive"))
    )
    (net (code "152") (name "unconnected-(U1-P0.10-Pad51)") (class "Default")
      (node (ref "U1") (pin "51") (pinfunction "P0.10_51") (pintype "passive"))
    )
    (net (code "153") (name "unconnected-(U1-P0.11-Pad52)") (class "Default")
      (node (ref "U1") (pin "52") (pinfunction "P0.11_52") (pintype "passive"))
    )
    (net (code "154") (name "unconnected-(U1-P0.12-Pad53)") (class "Default")
      (node (ref "U1") (pin "53") (pinfunction "P0.12_53") (pintype "passive"))
    )
    (net (code "155") (name "unconnected-(U1-P0.16-Pad54)") (class "Default")
      (node (ref "U1") (pin "54") (pinfunction "P0.16_54") (pintype "passive"))
    )
    (net (code "156") (name "unconnected-(U1-P0.24-Pad57)") (class "Default")
      (node (ref "U1") (pin "57") (pinfunction "P0.24_57") (pintype "passive"))
    )
    (net (code "157") (name "unconnected-(U1-P0.26-Pad58)") (class "Default")
      (node (ref "U1") (pin "58") (pinfunction "P0.26_58") (pintype "passive"))
    )
    (net (code "158") (name "unconnected-(U1-P0.28-Pad33)") (class "Default")
      (node (ref "U1") (pin "33") (pinfunction "P0.28_33") (pintype "passive"))
    )
    (net (code "159") (name "unconnected-(U1-P0.30-Pad37)") (class "Default")
      (node (ref "U1") (pin "37") (pinfunction "P0.30_37") (pintype "passive"))
    )
    (net (code "160") (name "unconnected-(U1-P0.31-Pad38)") (class "Default")
      (node (ref "U1") (pin "38") (pinfunction "P0.31_38") (pintype "passive"))
    )
    (net (code "161") (name "unconnected-(U1-P1.04-Pad55)") (class "Default")
      (node (ref "U1") (pin "55") (pinfunction "P1.04_55") (pintype "passive"))
    )
    (net (code "162") (name "unconnected-(U1-P1.08-Pad56)") (class "Default")
      (node (ref "U1") (pin "56") (pinfunction "P1.08_56") (pintype "passive"))
    )
    (net (code "163") (name "unconnected-(U1-P1.10-Pad34)") (class "Default")
      (node (ref "U1") (pin "34") (pinfunction "P1.10_34") (pintype "passive"))
    )
    (net (code "164") (name "unconnected-(U1-P1.11-Pad39)") (class "Default")
      (node (ref "U1") (pin "39") (pinfunction "P1.11_39") (pintype "passive"))
    )
    (net (code "165") (name "unconnected-(U1-P1.12-Pad40)") (class "Default")
      (node (ref "U1") (pin "40") (pinfunction "P1.12_40") (pintype "passive"))
    )
    (net (code "166") (name "unconnected-(U1-P1.13-Pad41)") (class "Default")
      (node (ref "U1") (pin "41") (pinfunction "P1.13_41") (pintype "passive"))
    )
    (net (code "167") (name "unconnected-(U1-P1.14-Pad42)") (class "Default")
      (node (ref "U1") (pin "42") (pinfunction "P1.14_42") (pintype "passive"))
    )
    (net (code "168") (name "unconnected-(U1-P1.15-Pad43)") (class "Default")
      (node (ref "U1") (pin "43") (pinfunction "P1.15_43") (pintype "passive"))
    )
    (net (code "169") (name "unconnected-(U2-SW2-Pad5)") (class "Default")
      (node (ref "U2") (pin "5") (pinfunction "SW2_5") (pintype "power_in"))
    )
    (net (code "170") (name "unconnected-(U2-VSET2-Pad16)") (class "Default")
      (node (ref "U2") (pin "16") (pinfunction "VSET2_16") (pintype "input"))
    )
  )
)
